# P1R4.net
KiCad netlist of a schematic drawn in EAGLE
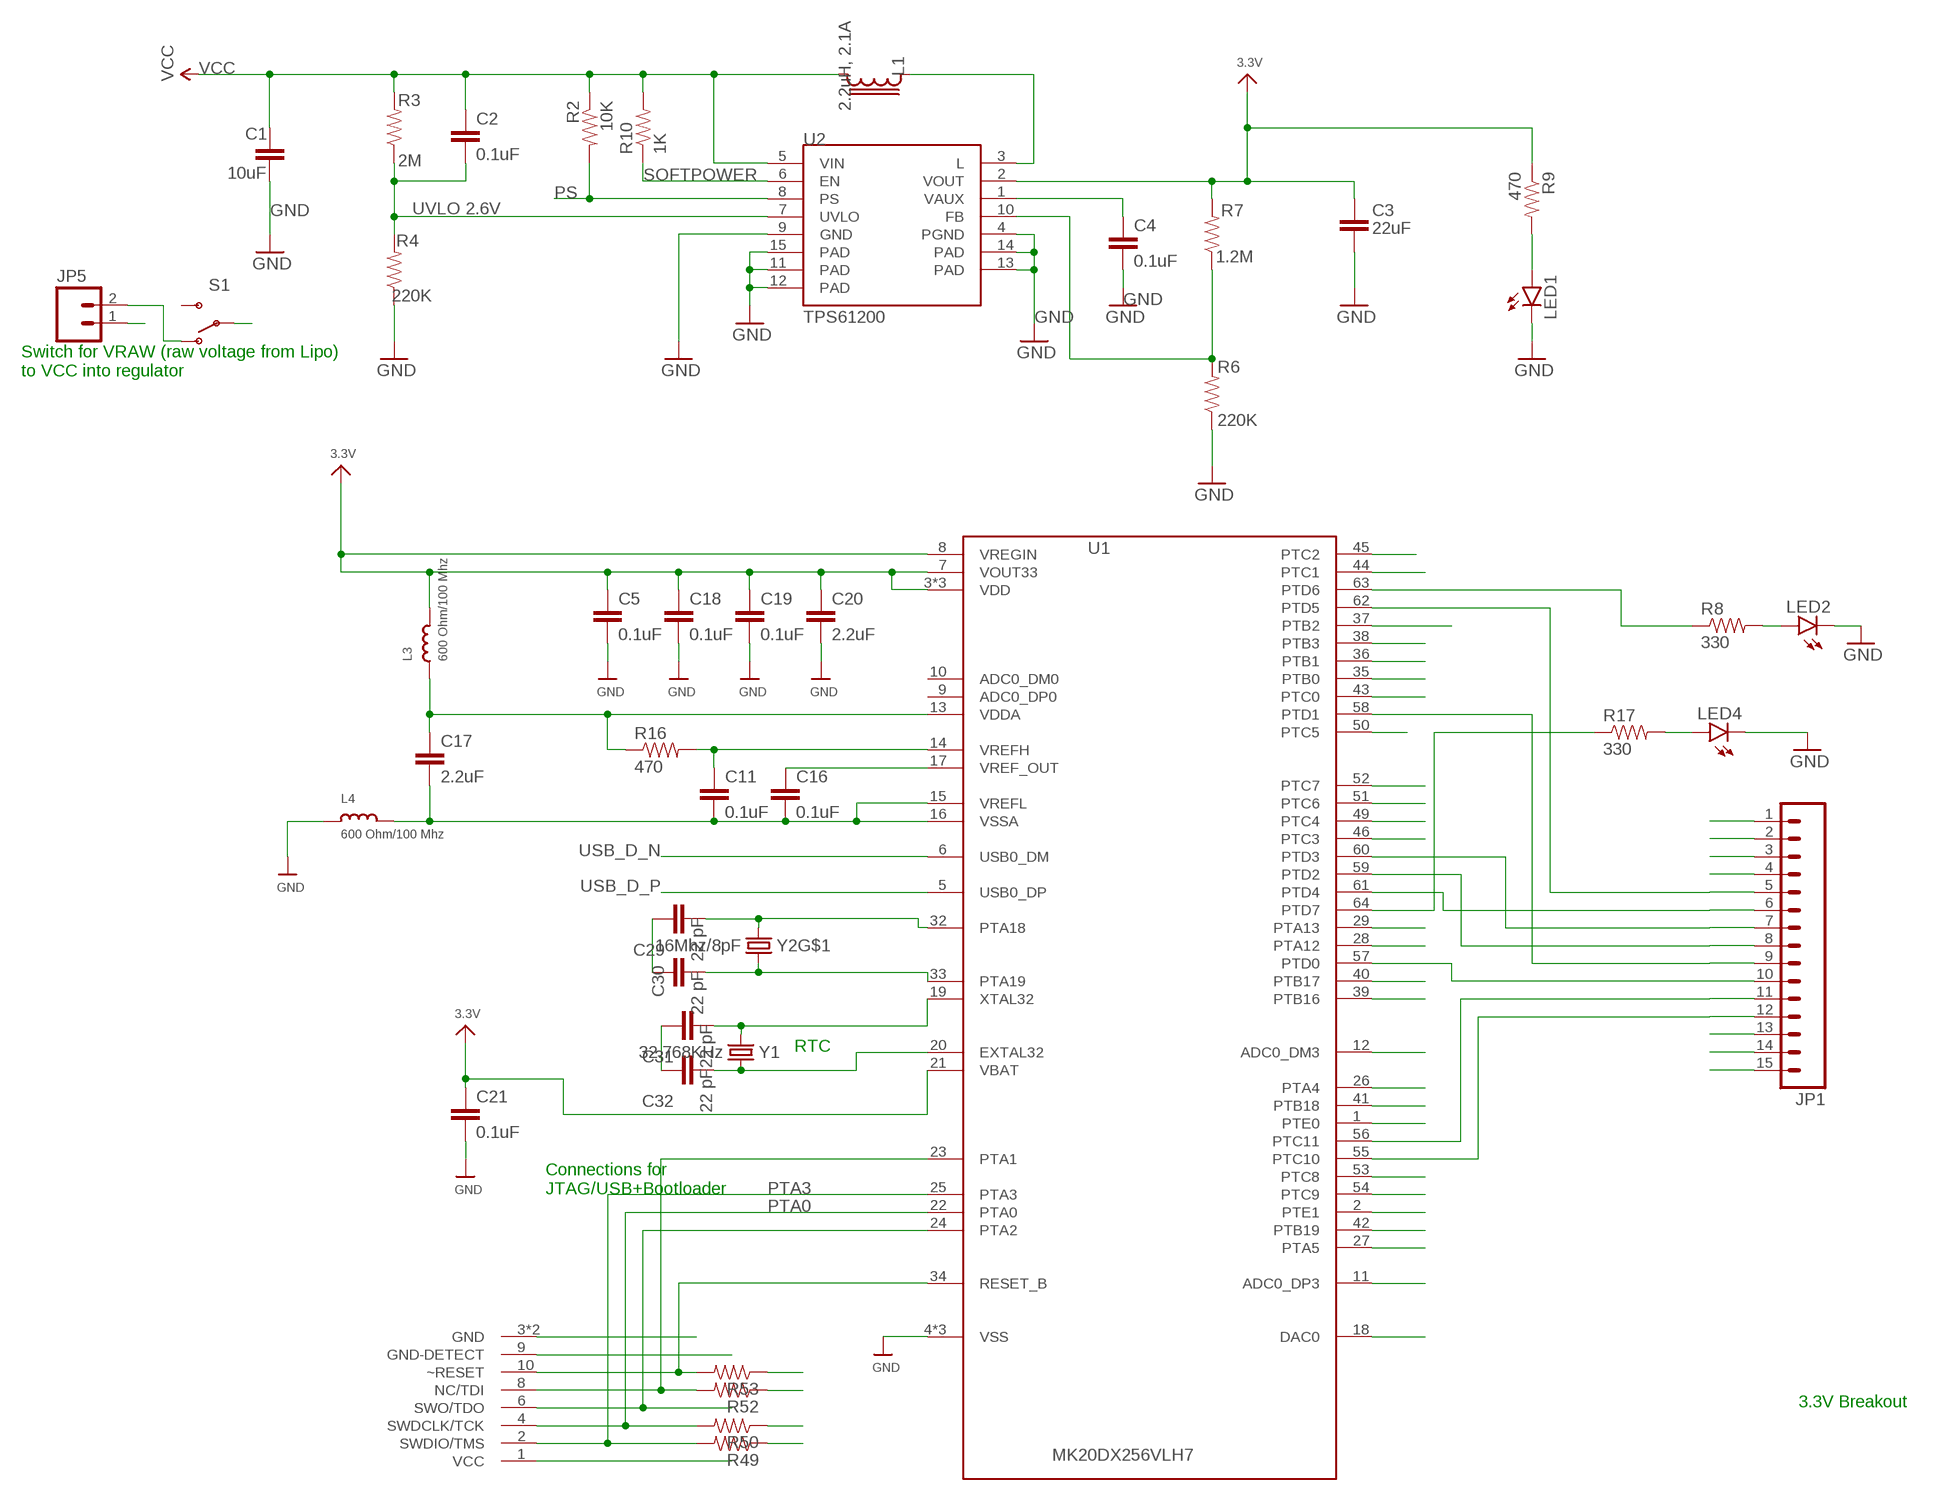
[diagram p0: schematic, sheet 1]
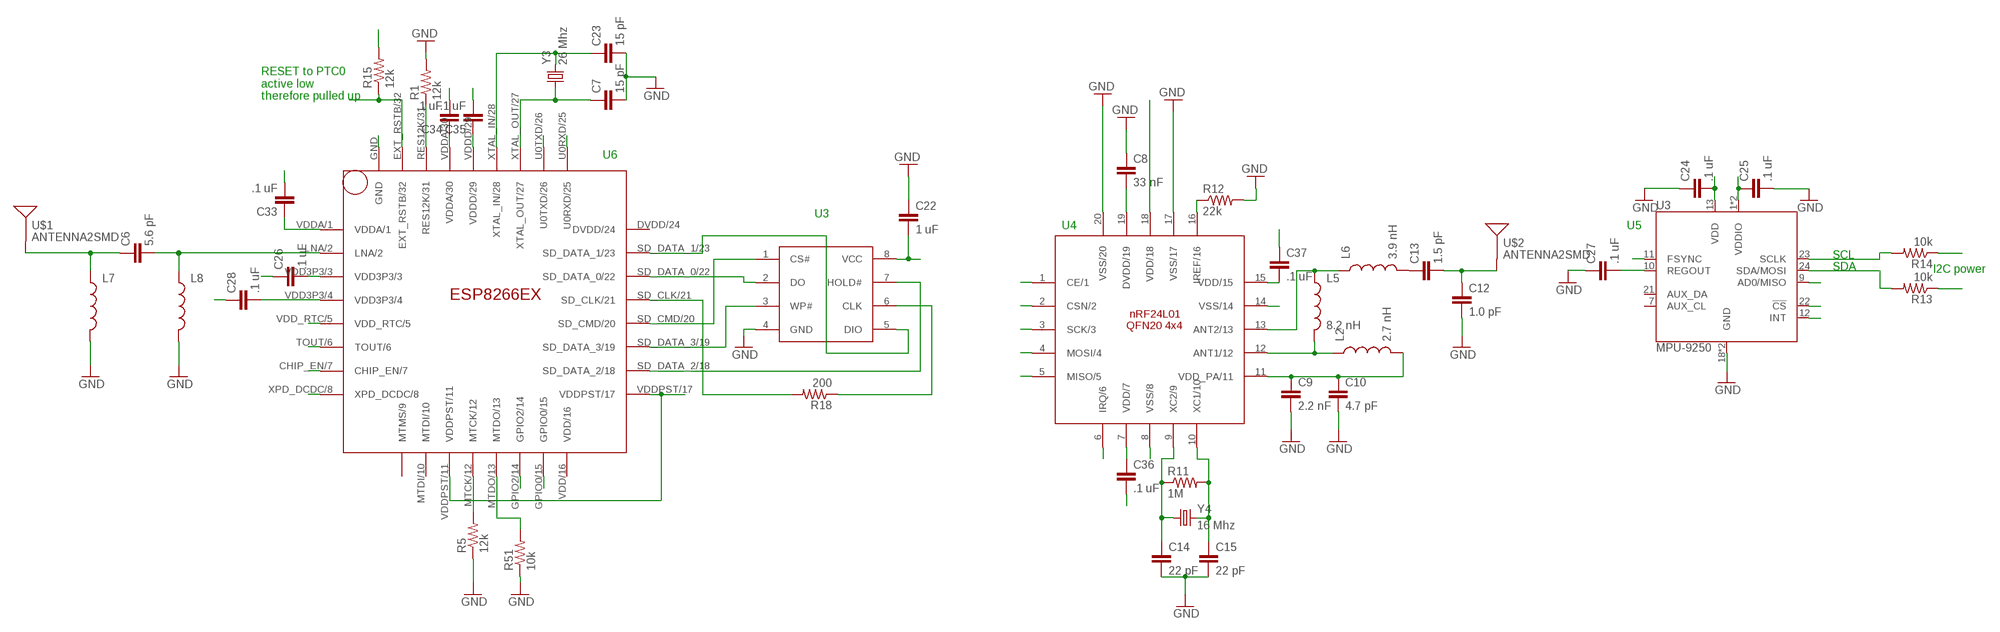
[diagram p1: schematic, sheet 2]
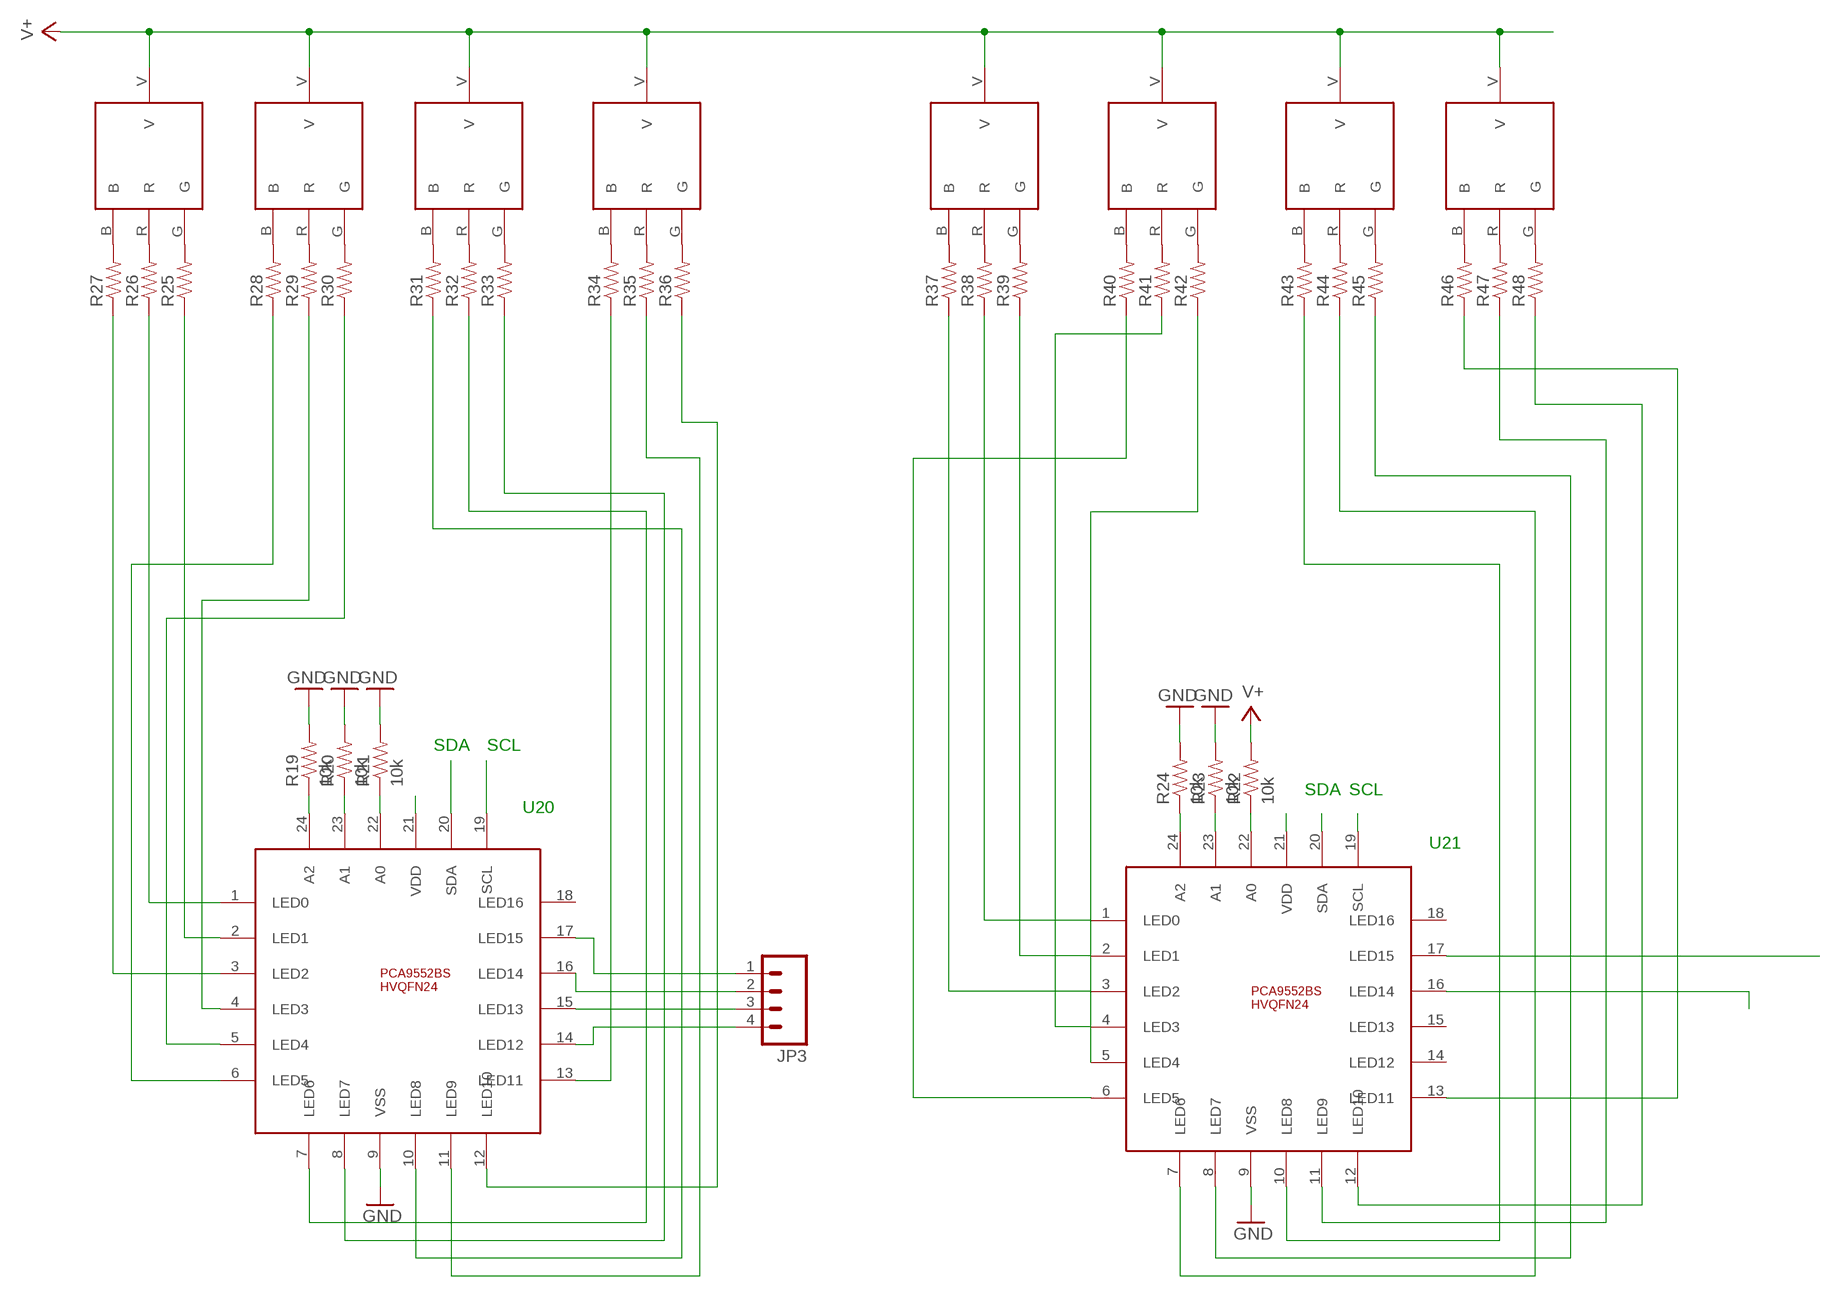
[diagram p2: schematic, sheet 3]

(export (version "E")
  (design (tool "Eeschema 10.0.6"))
  (components
    (comp (ref "C1")
      (value "10uF")
      (footprint "eagle-import:0603-CAP")
      (fields (field (name "MF") "Murata") (field (name "MPN") "GRM188R60J106ME47D"))
      (libsource (lib "eagle-import") (part "CAPACITOR-10UF"))
    )
    (comp (ref "C2")
      (value "0.1uF")
      (footprint "eagle-import:0603-CAP")
      (fields (field (name "MF") "Kemet") (field (name "MPN") "C0603C104J3RACTU"))
      (libsource (lib "eagle-import") (part "CAPACITOR-0.1UF"))
    )
    (comp (ref "C3")
      (value "22uF")
      (footprint "eagle-import:0603-CAP")
      (fields (field (name "MF") "Murata") (field (name "MPN") "GRM188R60J226MEA0D"))
      (libsource (lib "eagle-import") (part "CAPACITOR-22UF"))
    )
    (comp (ref "C4")
      (value "0.1uF")
      (footprint "eagle-import:0603-CAP")
      (fields (field (name "MF") "Kemet") (field (name "MPN") "C0603C104J3RACTU"))
      (libsource (lib "eagle-import") (part "CAPACITOR-0.1UF"))
    )
    (comp (ref "C5")
      (value "0.1uF")
      (footprint "eagle-import:0603-CAP")
      (fields (field (name "MF") "Kemet") (field (name "MPN") "C0603C104J3RACTU"))
      (libsource (lib "eagle-import") (part "CAPACITOR-0.1UF"))
    )
    (comp (ref "C11")
      (value "0.1uF")
      (footprint "eagle-import:0603-CAP")
      (fields (field (name "MF") "Kemet") (field (name "MPN") "C0603C104J3RACTU"))
      (libsource (lib "eagle-import") (part "CAPACITOR-0.1UF"))
    )
    (comp (ref "C16")
      (value "0.1uF")
      (footprint "eagle-import:0603-CAP")
      (fields (field (name "MF") "Kemet") (field (name "MPN") "C0603C104J3RACTU"))
      (libsource (lib "eagle-import") (part "CAPACITOR-0.1UF"))
    )
    (comp (ref "C17")
      (value "2.2uF")
      (footprint "eagle-import:0603-CAP")
      (fields (field (name "MF") "Kemet") (field (name "MPN") "C0603C225K4PACTU"))
      (libsource (lib "eagle-import") (part "CAPACITOR-2.2UF"))
    )
    (comp (ref "C18")
      (value "0.1uF")
      (footprint "eagle-import:0603-CAP")
      (fields (field (name "MF") "Kemet") (field (name "MPN") "C0603C104J3RACTU"))
      (libsource (lib "eagle-import") (part "CAPACITOR-0.1UF"))
    )
    (comp (ref "C19")
      (value "0.1uF")
      (footprint "eagle-import:0603-CAP")
      (fields (field (name "MF") "Kemet") (field (name "MPN") "C0603C104J3RACTU"))
      (libsource (lib "eagle-import") (part "CAPACITOR-0.1UF"))
    )
    (comp (ref "C20")
      (value "2.2uF")
      (footprint "eagle-import:0603-CAP")
      (fields (field (name "MF") "Kemet") (field (name "MPN") "C0603C225K4PACTU"))
      (libsource (lib "eagle-import") (part "CAPACITOR-2.2UF"))
    )
    (comp (ref "C21")
      (value "0.1uF")
      (footprint "eagle-import:0603-CAP")
      (fields (field (name "MF") "Kemet") (field (name "MPN") "C0603C104J3RACTU"))
      (libsource (lib "eagle-import") (part "CAPACITOR-0.1UF"))
    )
    (comp (ref "C29")
      (value "22 pF")
      (footprint "eagle-import:0603-CAP")
      (fields (field (name "MF") "Murata") (field (name "MPN") "GRM188R60J106ME47D"))
      (libsource (lib "eagle-import") (part "CAPACITOR-10UF"))
    )
    (comp (ref "C30")
      (value "22 pF")
      (footprint "eagle-import:0603-CAP")
      (fields (field (name "MF") "Murata") (field (name "MPN") "GRM188R60J106ME47D"))
      (libsource (lib "eagle-import") (part "CAPACITOR-10UF"))
    )
    (comp (ref "C31")
      (value "22 pF")
      (footprint "eagle-import:0603-CAP")
      (fields (field (name "MF") "Murata") (field (name "MPN") "GRM188R60J106ME47D"))
      (libsource (lib "eagle-import") (part "CAPACITOR-10UF"))
    )
    (comp (ref "C32")
      (value "22 pF")
      (footprint "eagle-import:0603-CAP")
      (fields (field (name "MF") "Murata") (field (name "MPN") "GRM188R60J106ME47D"))
      (libsource (lib "eagle-import") (part "CAPACITOR-10UF"))
    )
    (comp (ref "JP1")
      (value "M15")
      (footprint "eagle-import:1X15")
      (libsource (lib "eagle-import") (part "M15"))
    )
    (comp (ref "JP5")
      (value "M02PTH")
      (footprint "eagle-import:1X02")
      (libsource (lib "eagle-import") (part "M02PTH"))
    )
    (comp (ref "L1")
      (value "2.2uH, 2.1A")
      (footprint "eagle-import:LPS3015")
      (fields (field (name "MF") "Coilcraft") (field (name "MPN") "LPS3015-222MRB"))
      (libsource (lib "eagle-import") (part "LPS30152.2UH"))
    )
    (comp (ref "L3")
      (value "600 Ohm/100 Mhz")
      (footprint "eagle-import:0805")
      (fields (field (name "MF") "Taiyo Yuden") (field (name "MPN") "BK2125HM601-T"))
      (libsource (lib "eagle-import") (part "INDUCTOR-BK2125HM601-T"))
    )
    (comp (ref "L4")
      (value "600 Ohm/100 Mhz")
      (footprint "eagle-import:0805")
      (fields (field (name "MF") "Taiyo Yuden") (field (name "MPN") "BK2125HM601-T"))
      (libsource (lib "eagle-import") (part "INDUCTOR-BK2125HM601-T"))
    )
    (comp (ref "LED1")
      (value "LED-GREEN")
      (footprint "eagle-import:LED-0603")
      (fields (field (name "MF") "Avago") (field (name "MPN") "HSMG-C190"))
      (libsource (lib "eagle-import") (part "LED-GREEN"))
    )
    (comp (ref "LED2")
      (value "LED-GREEN")
      (footprint "eagle-import:LED-0603")
      (fields (field (name "MF") "Avago") (field (name "MPN") "HSMG-C190"))
      (libsource (lib "eagle-import") (part "LED-GREEN"))
    )
    (comp (ref "LED4")
      (value "LED-GREEN")
      (footprint "eagle-import:LED-0603")
      (fields (field (name "MF") "Avago") (field (name "MPN") "HSMG-C190"))
      (libsource (lib "eagle-import") (part "LED-GREEN"))
    )
    (comp (ref "R2")
      (value "10K")
      (footprint "eagle-import:0603-RES")
      (fields (field (name "MF") "Panasonic") (field (name "MPN") "ERJ-3GEYJ103V"))
      (libsource (lib "eagle-import") (part "RESISTOR-10K"))
    )
    (comp (ref "R3")
      (value "2M")
      (footprint "eagle-import:0603-RES")
      (fields (field (name "MF") "Panasonic") (field (name "MPN") "ERJ-3GEYJ205V"))
      (libsource (lib "eagle-import") (part "RESISTOR-2M"))
    )
    (comp (ref "R4")
      (value "220K")
      (footprint "eagle-import:0603-RES")
      (fields (field (name "MF") "Panasonic") (field (name "MPN") "ERJ-3GEYJ224V"))
      (libsource (lib "eagle-import") (part "RESISTOR-220K"))
    )
    (comp (ref "R6")
      (value "220K")
      (footprint "eagle-import:0603-RES")
      (fields (field (name "MF") "Panasonic") (field (name "MPN") "ERJ-3GEYJ224V"))
      (libsource (lib "eagle-import") (part "RESISTOR-220K"))
    )
    (comp (ref "R7")
      (value "1.2M")
      (footprint "eagle-import:0603-RES")
      (fields (field (name "MF") "Panasonic") (field (name "MPN") "ERJ-3GEYJ125V"))
      (libsource (lib "eagle-import") (part "RESISTOR-1.2M"))
    )
    (comp (ref "R8")
      (value "330")
      (footprint "eagle-import:0603-RES")
      (fields (field (name "MF") "Panasonic") (field (name "MPN") "ERJ-3GEYJ471V"))
      (libsource (lib "eagle-import") (part "RESISTOR-470"))
    )
    (comp (ref "R9")
      (value "470")
      (footprint "eagle-import:0603-RES")
      (fields (field (name "MF") "Panasonic") (field (name "MPN") "ERJ-3GEYJ471V"))
      (libsource (lib "eagle-import") (part "RESISTOR-470"))
    )
    (comp (ref "R10")
      (value "1K")
      (footprint "eagle-import:0603-RES")
      (fields (field (name "MF") "Panasonic") (field (name "MPN") "ERJ-3GEYJ102V"))
      (libsource (lib "eagle-import") (part "RESISTOR-1K"))
    )
    (comp (ref "R16")
      (value "470")
      (footprint "eagle-import:0603-RES")
      (fields (field (name "MF") "Panasonic") (field (name "MPN") "ERJ-3GEYJ471V"))
      (libsource (lib "eagle-import") (part "RESISTOR-470"))
    )
    (comp (ref "R17")
      (value "330")
      (footprint "eagle-import:0603-RES")
      (fields (field (name "MF") "Panasonic") (field (name "MPN") "ERJ-3GEYJ471V"))
      (libsource (lib "eagle-import") (part "RESISTOR-470"))
    )
    (comp (ref "R49")
      (value "RESISTOR0402-RES")
      (footprint "eagle-import:0402-RES")
      (libsource (lib "eagle-import") (part "RESISTOR0402-RES"))
    )
    (comp (ref "R50")
      (value "RESISTOR0402-RES")
      (footprint "eagle-import:0402-RES")
      (libsource (lib "eagle-import") (part "RESISTOR0402-RES"))
    )
    (comp (ref "R52")
      (value "RESISTOR0402-RES")
      (footprint "eagle-import:0402-RES")
      (libsource (lib "eagle-import") (part "RESISTOR0402-RES"))
    )
    (comp (ref "R53")
      (value "RESISTOR0402-RES")
      (footprint "eagle-import:0402-RES")
      (libsource (lib "eagle-import") (part "RESISTOR0402-RES"))
    )
    (comp (ref "S1")
      (value "SWITCH-SPDT-SMD-A")
      (footprint "eagle-import:SWITCH-SPST-SMD-A")
      (libsource (lib "eagle-import") (part "SWITCH-SPDT-SMD-A"))
    )
    (comp (ref "U$7")
      (value "2X5_0.05\"_CORTEX_DEBUGTH_NOKEY_UNSHROUDED")
      (footprint "eagle-import:2X5_0.05__TH_NS")
      (libsource (lib "eagle-import") (part "2X5_0.05{dblquote}_CORTEX_DEBUGTH_NOKEY_UNSHROUDED"))
    )
    (comp (ref "U1")
      (value "MK20DX256VLH7")
      (footprint "eagle-import:MK20DX256VLH7")
      (fields (field (name "MF") "Freescale"))
      (libsource (lib "eagle-import") (part "MK20DX256VLH7"))
    )
    (comp (ref "U2")
      (value "TPS61200")
      (footprint "eagle-import:QFN-10_PAD")
      (fields (field (name "MF") "Texas Instruments") (field (name "MPN") "TPS61200DRCR"))
      (libsource (lib "eagle-import") (part "TPS61200"))
    )
    (comp (ref "Y1")
      (value "32.768KHz")
      (footprint "eagle-import:CRYSTAL-TXC-7A")
      (fields (field (name "MF") "Epson Timing") (field (name "MPN") "FC-255 32.7680K-A3"))
      (libsource (lib "eagle-import") (part "CRYSTAL/32.768KHZ/SMD-TXC_7A"))
    )
    (comp (ref "Y2")
      (value "16Mhz/8pF")
      (footprint "eagle-import:CRYSTAL-SMD-5X3")
      (fields (field (name "MF") "ECS") (field (name "MPN") "ECS-160-8-30B-CKM"))
      (libsource (lib "eagle-import") (part "CRYSTAL/SMD-5X3-GND16MHZ/8PF"))
    )
    (comp (ref "JP3")
      (value "M04PTH")
      (footprint "eagle-import:1X04")
      (libsource (lib "eagle-import") (part "M04PTH"))
    )
    (comp (ref "R19")
      (value "10k")
      (footprint "eagle-import:0603-RES")
      (libsource (lib "eagle-import") (part "RESISTOR0603-RES"))
    )
    (comp (ref "R20")
      (value "10k")
      (footprint "eagle-import:0603-RES")
      (libsource (lib "eagle-import") (part "RESISTOR0603-RES"))
    )
    (comp (ref "R21")
      (value "10k")
      (footprint "eagle-import:0603-RES")
      (libsource (lib "eagle-import") (part "RESISTOR0603-RES"))
    )
    (comp (ref "R22")
      (value "10k")
      (footprint "eagle-import:0603-RES")
      (libsource (lib "eagle-import") (part "RESISTOR0603-RES"))
    )
    (comp (ref "R23")
      (value "10k")
      (footprint "eagle-import:0603-RES")
      (libsource (lib "eagle-import") (part "RESISTOR0603-RES"))
    )
    (comp (ref "R24")
      (value "10k")
      (footprint "eagle-import:0603-RES")
      (libsource (lib "eagle-import") (part "RESISTOR0603-RES"))
    )
    (comp (ref "R25")
      (value "RESISTOR0402-RES")
      (footprint "eagle-import:0402-RES")
      (libsource (lib "eagle-import") (part "RESISTOR0402-RES"))
    )
    (comp (ref "R26")
      (value "RESISTOR0402-RES")
      (footprint "eagle-import:0402-RES")
      (libsource (lib "eagle-import") (part "RESISTOR0402-RES"))
    )
    (comp (ref "R27")
      (value "RESISTOR0402-RES")
      (footprint "eagle-import:0402-RES")
      (libsource (lib "eagle-import") (part "RESISTOR0402-RES"))
    )
    (comp (ref "R28")
      (value "RESISTOR0402-RES")
      (footprint "eagle-import:0402-RES")
      (libsource (lib "eagle-import") (part "RESISTOR0402-RES"))
    )
    (comp (ref "R29")
      (value "RESISTOR0402-RES")
      (footprint "eagle-import:0402-RES")
      (libsource (lib "eagle-import") (part "RESISTOR0402-RES"))
    )
    (comp (ref "R30")
      (value "RESISTOR0402-RES")
      (footprint "eagle-import:0402-RES")
      (libsource (lib "eagle-import") (part "RESISTOR0402-RES"))
    )
    (comp (ref "R31")
      (value "RESISTOR0402-RES")
      (footprint "eagle-import:0402-RES")
      (libsource (lib "eagle-import") (part "RESISTOR0402-RES"))
    )
    (comp (ref "R32")
      (value "RESISTOR0402-RES")
      (footprint "eagle-import:0402-RES")
      (libsource (lib "eagle-import") (part "RESISTOR0402-RES"))
    )
    (comp (ref "R33")
      (value "RESISTOR0402-RES")
      (footprint "eagle-import:0402-RES")
      (libsource (lib "eagle-import") (part "RESISTOR0402-RES"))
    )
    (comp (ref "R34")
      (value "RESISTOR0402-RES")
      (footprint "eagle-import:0402-RES")
      (libsource (lib "eagle-import") (part "RESISTOR0402-RES"))
    )
    (comp (ref "R35")
      (value "RESISTOR0402-RES")
      (footprint "eagle-import:0402-RES")
      (libsource (lib "eagle-import") (part "RESISTOR0402-RES"))
    )
    (comp (ref "R36")
      (value "RESISTOR0402-RES")
      (footprint "eagle-import:0402-RES")
      (libsource (lib "eagle-import") (part "RESISTOR0402-RES"))
    )
    (comp (ref "R37")
      (value "RESISTOR0402-RES")
      (footprint "eagle-import:0402-RES")
      (libsource (lib "eagle-import") (part "RESISTOR0402-RES"))
    )
    (comp (ref "R38")
      (value "RESISTOR0402-RES")
      (footprint "eagle-import:0402-RES")
      (libsource (lib "eagle-import") (part "RESISTOR0402-RES"))
    )
    (comp (ref "R39")
      (value "RESISTOR0402-RES")
      (footprint "eagle-import:0402-RES")
      (libsource (lib "eagle-import") (part "RESISTOR0402-RES"))
    )
    (comp (ref "R40")
      (value "RESISTOR0402-RES")
      (footprint "eagle-import:0402-RES")
      (libsource (lib "eagle-import") (part "RESISTOR0402-RES"))
    )
    (comp (ref "R41")
      (value "RESISTOR0402-RES")
      (footprint "eagle-import:0402-RES")
      (libsource (lib "eagle-import") (part "RESISTOR0402-RES"))
    )
    (comp (ref "R42")
      (value "RESISTOR0402-RES")
      (footprint "eagle-import:0402-RES")
      (libsource (lib "eagle-import") (part "RESISTOR0402-RES"))
    )
    (comp (ref "R43")
      (value "RESISTOR0402-RES")
      (footprint "eagle-import:0402-RES")
      (libsource (lib "eagle-import") (part "RESISTOR0402-RES"))
    )
    (comp (ref "R44")
      (value "RESISTOR0402-RES")
      (footprint "eagle-import:0402-RES")
      (libsource (lib "eagle-import") (part "RESISTOR0402-RES"))
    )
    (comp (ref "R45")
      (value "RESISTOR0402-RES")
      (footprint "eagle-import:0402-RES")
      (libsource (lib "eagle-import") (part "RESISTOR0402-RES"))
    )
    (comp (ref "R46")
      (value "RESISTOR0402-RES")
      (footprint "eagle-import:0402-RES")
      (libsource (lib "eagle-import") (part "RESISTOR0402-RES"))
    )
    (comp (ref "R47")
      (value "RESISTOR0402-RES")
      (footprint "eagle-import:0402-RES")
      (libsource (lib "eagle-import") (part "RESISTOR0402-RES"))
    )
    (comp (ref "R48")
      (value "RESISTOR0402-RES")
      (footprint "eagle-import:0402-RES")
      (libsource (lib "eagle-import") (part "RESISTOR0402-RES"))
    )
    (comp (ref "U$8")
      (value "LTST-C19FD1WT")
      (footprint "eagle-import:LTST-C19FD1WT")
      (libsource (lib "eagle-import") (part "LTST-C19FD1WT"))
    )
    (comp (ref "U$11")
      (value "LTST-C19FD1WT")
      (footprint "eagle-import:LTST-C19FD1WT")
      (libsource (lib "eagle-import") (part "LTST-C19FD1WT"))
    )
    (comp (ref "U$13")
      (value "LTST-C19FD1WT")
      (footprint "eagle-import:LTST-C19FD1WT")
      (libsource (lib "eagle-import") (part "LTST-C19FD1WT"))
    )
    (comp (ref "U$14")
      (value "LTST-C19FD1WT")
      (footprint "eagle-import:LTST-C19FD1WT")
      (libsource (lib "eagle-import") (part "LTST-C19FD1WT"))
    )
    (comp (ref "U$15")
      (value "LTST-C19FD1WT")
      (footprint "eagle-import:LTST-C19FD1WT")
      (libsource (lib "eagle-import") (part "LTST-C19FD1WT"))
    )
    (comp (ref "U$16")
      (value "LTST-C19FD1WT")
      (footprint "eagle-import:LTST-C19FD1WT")
      (libsource (lib "eagle-import") (part "LTST-C19FD1WT"))
    )
    (comp (ref "U$17")
      (value "LTST-C19FD1WT")
      (footprint "eagle-import:LTST-C19FD1WT")
      (libsource (lib "eagle-import") (part "LTST-C19FD1WT"))
    )
    (comp (ref "U$18")
      (value "LTST-C19FD1WT")
      (footprint "eagle-import:LTST-C19FD1WT")
      (libsource (lib "eagle-import") (part "LTST-C19FD1WT"))
    )
    (comp (ref "U$20")
      (value "PCA9552BS")
      (footprint "eagle-import:HVQFN24")
      (libsource (lib "eagle-import") (part "PCA9552BS"))
    )
    (comp (ref "U$21")
      (value "PCA9552BS")
      (footprint "eagle-import:HVQFN24")
      (libsource (lib "eagle-import") (part "PCA9552BS"))
    )
    (comp (ref "C6")
      (value "5.6 pF")
      (footprint "eagle-import:0603-CAP")
      (libsource (lib "eagle-import") (part "CAP0603-CAP"))
    )
    (comp (ref "C7")
      (value "15 pF")
      (footprint "eagle-import:0603-CAP")
      (libsource (lib "eagle-import") (part "CAP0603-CAP"))
    )
    (comp (ref "C8")
      (value "33 nF")
      (footprint "eagle-import:0603-CAP")
      (libsource (lib "eagle-import") (part "CAP0603-CAP"))
    )
    (comp (ref "C9")
      (value "2.2 nF")
      (footprint "eagle-import:0603-CAP")
      (libsource (lib "eagle-import") (part "CAP0603-CAP"))
    )
    (comp (ref "C10")
      (value "4.7 pF")
      (footprint "eagle-import:0603-CAP")
      (libsource (lib "eagle-import") (part "CAP0603-CAP"))
    )
    (comp (ref "C12")
      (value "1.0 pF")
      (footprint "eagle-import:0603-CAP")
      (libsource (lib "eagle-import") (part "CAP0603-CAP"))
    )
    (comp (ref "C13")
      (value "1.5 pF")
      (footprint "eagle-import:0603-CAP")
      (libsource (lib "eagle-import") (part "CAP0603-CAP"))
    )
    (comp (ref "C14")
      (value "22 pF")
      (footprint "eagle-import:0603-CAP")
      (libsource (lib "eagle-import") (part "CAP0603-CAP"))
    )
    (comp (ref "C15")
      (value "22 pF")
      (footprint "eagle-import:0603-CAP")
      (libsource (lib "eagle-import") (part "CAP0603-CAP"))
    )
    (comp (ref "C22")
      (value "1 uF")
      (footprint "eagle-import:0603-CAP")
      (libsource (lib "eagle-import") (part "CAP0603-CAP"))
    )
    (comp (ref "C23")
      (value "15 pF")
      (footprint "eagle-import:0603-CAP")
      (libsource (lib "eagle-import") (part "CAP0603-CAP"))
    )
    (comp (ref "C24")
      (value ".1 uF")
      (footprint "eagle-import:0603-CAP")
      (libsource (lib "eagle-import") (part "CAP0603-CAP"))
    )
    (comp (ref "C25")
      (value ".1 uF")
      (footprint "eagle-import:0603-CAP")
      (libsource (lib "eagle-import") (part "CAP0603-CAP"))
    )
    (comp (ref "C26")
      (value ".1 uF")
      (footprint "eagle-import:0603-CAP")
      (libsource (lib "eagle-import") (part "CAP0603-CAP"))
    )
    (comp (ref "C27")
      (value ".1 uF")
      (footprint "eagle-import:0603-CAP")
      (libsource (lib "eagle-import") (part "CAP0603-CAP"))
    )
    (comp (ref "C28")
      (value ".1 uF")
      (footprint "eagle-import:0603-CAP")
      (libsource (lib "eagle-import") (part "CAP0603-CAP"))
    )
    (comp (ref "C33")
      (value ".1 uF")
      (footprint "eagle-import:0603-CAP")
      (libsource (lib "eagle-import") (part "CAP0603-CAP"))
    )
    (comp (ref "C34")
      (value ".1 uF")
      (footprint "eagle-import:0603-CAP")
      (libsource (lib "eagle-import") (part "CAP0603-CAP"))
    )
    (comp (ref "C35")
      (value ".1 uF")
      (footprint "eagle-import:0603-CAP")
      (libsource (lib "eagle-import") (part "CAP0603-CAP"))
    )
    (comp (ref "C36")
      (value ".1 uF")
      (footprint "eagle-import:0603-CAP")
      (libsource (lib "eagle-import") (part "CAP0603-CAP"))
    )
    (comp (ref "C37")
      (value ".1 uF")
      (footprint "eagle-import:0603-CAP")
      (libsource (lib "eagle-import") (part "CAP0603-CAP"))
    )
    (comp (ref "L2")
      (value "2.7 nH")
      (footprint "eagle-import:C0402")
      (libsource (lib "eagle-import") (part "INDUCTOR0402"))
    )
    (comp (ref "L5")
      (value "8.2 nH")
      (footprint "eagle-import:C0402")
      (libsource (lib "eagle-import") (part "INDUCTOR0402"))
    )
    (comp (ref "L6")
      (value "3.9 nH")
      (footprint "eagle-import:C0402")
      (libsource (lib "eagle-import") (part "INDUCTOR0402"))
    )
    (comp (ref "L7")
      (value "INDUCTOR30OHM,1.8A")
      (footprint "eagle-import:0603")
      (libsource (lib "eagle-import") (part "INDUCTOR30OHM,1.8A"))
    )
    (comp (ref "L8")
      (value "INDUCTOR30OHM,1.8A")
      (footprint "eagle-import:0603")
      (libsource (lib "eagle-import") (part "INDUCTOR30OHM,1.8A"))
    )
    (comp (ref "R1")
      (value "12k")
      (footprint "eagle-import:0603-RES")
      (libsource (lib "eagle-import") (part "SparkFun-Resistors_RESISTOR0603-RES"))
    )
    (comp (ref "R5")
      (value "12k")
      (footprint "eagle-import:0603-RES")
      (libsource (lib "eagle-import") (part "SparkFun-Resistors_RESISTOR0603-RES"))
    )
    (comp (ref "R11")
      (value "1M")
      (footprint "eagle-import:0603-RES")
      (libsource (lib "eagle-import") (part "SparkFun-Resistors_RESISTOR0603-RES"))
    )
    (comp (ref "R12")
      (value "22k")
      (footprint "eagle-import:0603-RES")
      (libsource (lib "eagle-import") (part "SparkFun-Resistors_RESISTOR0603-RES"))
    )
    (comp (ref "R13")
      (value "10k")
      (footprint "eagle-import:0603-RES")
      (libsource (lib "eagle-import") (part "SparkFun-Resistors_RESISTOR0603-RES"))
    )
    (comp (ref "R14")
      (value "10k")
      (footprint "eagle-import:0603-RES")
      (libsource (lib "eagle-import") (part "SparkFun-Resistors_RESISTOR0603-RES"))
    )
    (comp (ref "R15")
      (value "12k")
      (footprint "eagle-import:0603-RES")
      (libsource (lib "eagle-import") (part "SparkFun-Resistors_RESISTOR0603-RES"))
    )
    (comp (ref "R18")
      (value "200")
      (footprint "eagle-import:0603-RES")
      (libsource (lib "eagle-import") (part "SparkFun-Resistors_RESISTOR0603-RES"))
    )
    (comp (ref "R51")
      (value "10k")
      (footprint "eagle-import:0603-RES")
      (libsource (lib "eagle-import") (part "SparkFun-Resistors_RESISTOR0603-RES"))
    )
    (comp (ref "U$1")
      (value "ANTENNA2SMD")
      (footprint "eagle-import:ANTENNA-CHIP2")
      (libsource (lib "eagle-import") (part "ANTENNA2SMD"))
    )
    (comp (ref "U$2")
      (value "ANTENNA2SMD")
      (footprint "eagle-import:ANTENNA-CHIP2")
      (libsource (lib "eagle-import") (part "ANTENNA2SMD"))
    )
    (comp (ref "U$3")
      (value "25Q40")
      (footprint "eagle-import:SOP8")
      (libsource (lib "eagle-import") (part "25Q40"))
    )
    (comp (ref "U$4")
      (value "NRF24L01")
      (footprint "eagle-import:QFN20(4X4)")
      (libsource (lib "eagle-import") (part "NRF24L01"))
    )
    (comp (ref "U$6")
      (value "ESP8266EX")
      (footprint "eagle-import:QFN32")
      (libsource (lib "eagle-import") (part "ESP8266EX"))
    )
    (comp (ref "U3")
      (value "MPU-9250")
      (footprint "eagle-import:QFN-24_3MM")
      (libsource (lib "eagle-import") (part "MPU-9250"))
    )
    (comp (ref "Y3")
      (value "26 Mhz")
      (footprint "eagle-import:CRYSTAL-SMD-5X3")
      (libsource (lib "eagle-import") (part "CRYSTAL5X3"))
    )
    (comp (ref "Y4")
      (value "16 Mhz")
      (footprint "eagle-import:CRYSTAL-SMD-5X3")
      (libsource (lib "eagle-import") (part "CRYSTAL5X3"))
    )
  )
  (nets
    (net (code "1") (name "3.3V") (class "Default")
      (node (ref "C18") (pin "1") (pinfunction "1_1") (pintype "passive"))
      (node (ref "C19") (pin "1") (pinfunction "1_1") (pintype "passive"))
      (node (ref "C20") (pin "1") (pinfunction "1_1") (pintype "passive"))
      (node (ref "C21") (pin "1") (pinfunction "1_1") (pintype "passive"))
      (node (ref "C22") (pin "2") (pinfunction "2_2") (pintype "passive"))
      (node (ref "C24") (pin "2") (pinfunction "2_2") (pintype "passive"))
      (node (ref "C25") (pin "1") (pinfunction "1_1") (pintype "passive"))
      (node (ref "C26") (pin "2") (pinfunction "2_2") (pintype "passive"))
      (node (ref "C28") (pin "2") (pinfunction "2_2") (pintype "passive"))
      (node (ref "C3") (pin "1") (pinfunction "1_1") (pintype "passive"))
      (node (ref "C33") (pin "1") (pinfunction "1_1") (pintype "passive"))
      (node (ref "C34") (pin "1") (pinfunction "1_1") (pintype "passive"))
      (node (ref "C35") (pin "1") (pinfunction "1_1") (pintype "passive"))
      (node (ref "C36") (pin "1") (pinfunction "1_1") (pintype "passive"))
      (node (ref "C37") (pin "2") (pinfunction "2_2") (pintype "passive"))
      (node (ref "C5") (pin "1") (pinfunction "1_1") (pintype "passive"))
      (node (ref "JP1") (pin "13") (pinfunction "13_13") (pintype "passive"))
      (node (ref "JP1") (pin "14") (pinfunction "14_14") (pintype "passive"))
      (node (ref "JP1") (pin "15") (pinfunction "15_15") (pintype "passive"))
      (node (ref "L3") (pin "2") (pinfunction "2_2") (pintype "passive"))
      (node (ref "R13") (pin "1") (pinfunction "1_1") (pintype "passive"))
      (node (ref "R14") (pin "1") (pinfunction "1_1") (pintype "passive"))
      (node (ref "R15") (pin "2") (pinfunction "2_2") (pintype "passive"))
      (node (ref "R22") (pin "2") (pinfunction "2_2") (pintype "passive"))
      (node (ref "R49") (pin "1") (pinfunction "1_1") (pintype "passive"))
      (node (ref "R52") (pin "1") (pinfunction "1_1") (pintype "passive"))
      (node (ref "R53") (pin "1") (pinfunction "1_1") (pintype "passive"))
      (node (ref "R7") (pin "2") (pinfunction "2_2") (pintype "passive"))
      (node (ref "R9") (pin "1") (pinfunction "1_1") (pintype "passive"))
      (node (ref "U$11") (pin "V") (pinfunction "V_V") (pintype "bidirectional"))
      (node (ref "U$13") (pin "V") (pinfunction "V_V") (pintype "bidirectional"))
      (node (ref "U$14") (pin "V") (pinfunction "V_V") (pintype "bidirectional"))
      (node (ref "U$15") (pin "V") (pinfunction "V_V") (pintype "bidirectional"))
      (node (ref "U$16") (pin "V") (pinfunction "V_V") (pintype "bidirectional"))
      (node (ref "U$17") (pin "V") (pinfunction "V_V") (pintype "bidirectional"))
      (node (ref "U$18") (pin "V") (pinfunction "V_V") (pintype "bidirectional"))
      (node (ref "U$20") (pin "21") (pinfunction "VDD_21") (pintype "bidirectional"))
      (node (ref "U$21") (pin "21") (pinfunction "VDD_21") (pintype "bidirectional"))
      (node (ref "U$3") (pin "8") (pinfunction "VCC_8") (pintype "bidirectional"))
      (node (ref "U$4") (pin "15") (pinfunction "VDD/15_15") (pintype "bidirectional"))
      (node (ref "U$4") (pin "18") (pinfunction "VDD/18_18") (pintype "bidirectional"))
      (node (ref "U$4") (pin "7") (pinfunction "VDD/7_7") (pintype "bidirectional"))
      (node (ref "U$6") (pin "VDD3P3/3") (pinfunction "VDD3P3/3_VDD3P3/3") (pintype "bidirectional"))
      (node (ref "U$6") (pin "VDD3P3/4") (pinfunction "VDD3P3/4_VDD3P3/4") (pintype "bidirectional"))
      (node (ref "U$6") (pin "VDDA/1") (pinfunction "VDDA/1_VDDA/1") (pintype "bidirectional"))
      (node (ref "U$6") (pin "VDDA/30") (pinfunction "VDDA/30_VDDA/30") (pintype "bidirectional"))
      (node (ref "U$6") (pin "VDDD/29") (pinfunction "VDDD/29_VDDD/29") (pintype "bidirectional"))
      (node (ref "U$6") (pin "VDDPST/11") (pinfunction "VDDPST/11_VDDPST/11") (pintype "bidirectional"))
      (node (ref "U$6") (pin "VDDPST/17") (pinfunction "VDDPST/17_VDDPST/17") (pintype "bidirectional"))
      (node (ref "U$7") (pin "1") (pinfunction "VCC_1") (pintype "bidirectional"))
      (node (ref "U$8") (pin "V") (pinfunction "V_V") (pintype "bidirectional"))
      (node (ref "U1") (pin "21") (pinfunction "VBAT_21") (pintype "bidirectional"))
      (node (ref "U1") (pin "3") (pinfunction "VDD_3") (pintype "bidirectional"))
      (node (ref "U1") (pin "30") (pinfunction "VDD_30") (pintype "bidirectional"))
      (node (ref "U1") (pin "48") (pinfunction "VDD_48") (pintype "bidirectional"))
      (node (ref "U1") (pin "7") (pinfunction "VOUT33_7") (pintype "bidirectional"))
      (node (ref "U1") (pin "8") (pinfunction "VREGIN_8") (pintype "bidirectional"))
      (node (ref "U2") (pin "2") (pinfunction "VOUT_2") (pintype "passive"))
      (node (ref "U3") (pin "1") (pinfunction "VDDIO_1") (pintype "bidirectional"))
      (node (ref "U3") (pin "13") (pinfunction "VDD_13") (pintype "bidirectional"))
      (node (ref "U3") (pin "22") (pinfunction "~{CS}_22") (pintype "bidirectional"))
      (node (ref "U3") (pin "8") (pinfunction "VDDIO_8") (pintype "bidirectional"))
    )
    (net (code "2") (name "AD0") (class "Default")
      (node (ref "U1") (pin "45") (pinfunction "PTC2_45") (pintype "bidirectional"))
      (node (ref "U3") (pin "9") (pinfunction "AD0/MISO_9") (pintype "bidirectional"))
    )
    (net (code "3") (name "GND") (class "Default")
      (node (ref "C1") (pin "2") (pinfunction "2_2") (pintype "passive"))
      (node (ref "C10") (pin "2") (pinfunction "2_2") (pintype "passive"))
      (node (ref "C12") (pin "2") (pinfunction "2_2") (pintype "passive"))
      (node (ref "C14") (pin "2") (pinfunction "2_2") (pintype "passive"))
      (node (ref "C15") (pin "2") (pinfunction "2_2") (pintype "passive"))
      (node (ref "C18") (pin "2") (pinfunction "2_2") (pintype "passive"))
      (node (ref "C19") (pin "2") (pinfunction "2_2") (pintype "passive"))
      (node (ref "C20") (pin "2") (pinfunction "2_2") (pintype "passive"))
      (node (ref "C21") (pin "2") (pinfunction "2_2") (pintype "passive"))
      (node (ref "C22") (pin "1") (pinfunction "1_1") (pintype "passive"))
      (node (ref "C23") (pin "2") (pinfunction "2_2") (pintype "passive"))
      (node (ref "C24") (pin "1") (pinfunction "1_1") (pintype "passive"))
      (node (ref "C25") (pin "2") (pinfunction "2_2") (pintype "passive"))
      (node (ref "C26") (pin "1") (pinfunction "1_1") (pintype "passive"))
      (node (ref "C27") (pin "1") (pinfunction "1_1") (pintype "passive"))
      (node (ref "C28") (pin "1") (pinfunction "1_1") (pintype "passive"))
      (node (ref "C29") (pin "1") (pinfunction "1_1") (pintype "passive"))
      (node (ref "C3") (pin "2") (pinfunction "2_2") (pintype "passive"))
      (node (ref "C30") (pin "1") (pinfunction "1_1") (pintype "passive"))
      (node (ref "C31") (pin "1") (pinfunction "1_1") (pintype "passive"))
      (node (ref "C32") (pin "1") (pinfunction "1_1") (pintype "passive"))
      (node (ref "C33") (pin "2") (pinfunction "2_2") (pintype "passive"))
      (node (ref "C34") (pin "2") (pinfunction "2_2") (pintype "passive"))
      (node (ref "C35") (pin "2") (pinfunction "2_2") (pintype "passive"))
      (node (ref "C36") (pin "2") (pinfunction "2_2") (pintype "passive"))
      (node (ref "C37") (pin "1") (pinfunction "1_1") (pintype "passive"))
      (node (ref "C4") (pin "2") (pinfunction "2_2") (pintype "passive"))
      (node (ref "C5") (pin "2") (pinfunction "2_2") (pintype "passive"))
      (node (ref "C7") (pin "2") (pinfunction "2_2") (pintype "passive"))
      (node (ref "C8") (pin "1") (pinfunction "1_1") (pintype "passive"))
      (node (ref "C9") (pin "2") (pinfunction "2_2") (pintype "passive"))
      (node (ref "JP1") (pin "1") (pinfunction "1_1") (pintype "passive"))
      (node (ref "JP1") (pin "2") (pinfunction "2_2") (pintype "passive"))
      (node (ref "JP1") (pin "3") (pinfunction "3_3") (pintype "passive"))
      (node (ref "JP1") (pin "4") (pinfunction "4_4") (pintype "passive"))
      (node (ref "JP5") (pin "1") (pinfunction "1_1") (pintype "passive"))
      (node (ref "L4") (pin "1") (pinfunction "1_1") (pintype "passive"))
      (node (ref "L7") (pin "2") (pinfunction "2_2") (pintype "passive"))
      (node (ref "L8") (pin "2") (pinfunction "2_2") (pintype "passive"))
      (node (ref "LED1") (pin "C") (pinfunction "C_C") (pintype "passive"))
      (node (ref "LED2") (pin "C") (pinfunction "C_C") (pintype "passive"))
      (node (ref "LED4") (pin "C") (pinfunction "C_C") (pintype "passive"))
      (node (ref "R1") (pin "2") (pinfunction "2_2") (pintype "passive"))
      (node (ref "R12") (pin "2") (pinfunction "2_2") (pintype "passive"))
      (node (ref "R19") (pin "2") (pinfunction "2_2") (pintype "passive"))
      (node (ref "R20") (pin "2") (pinfunction "2_2") (pintype "passive"))
      (node (ref "R21") (pin "2") (pinfunction "2_2") (pintype "passive"))
      (node (ref "R23") (pin "2") (pinfunction "2_2") (pintype "passive"))
      (node (ref "R24") (pin "2") (pinfunction "2_2") (pintype "passive"))
      (node (ref "R4") (pin "1") (pinfunction "1_1") (pintype "passive"))
      (node (ref "R5") (pin "1") (pinfunction "1_1") (pintype "passive"))
      (node (ref "R50") (pin "1") (pinfunction "1_1") (pintype "passive"))
      (node (ref "R51") (pin "1") (pinfunction "1_1") (pintype "passive"))
      (node (ref "R6") (pin "1") (pinfunction "1_1") (pintype "passive"))
      (node (ref "U$20") (pin "9") (pinfunction "VSS_9") (pintype "bidirectional"))
      (node (ref "U$21") (pin "9") (pinfunction "VSS_9") (pintype "bidirectional"))
      (node (ref "U$3") (pin "4") (pinfunction "GND_4") (pintype "bidirectional"))
      (node (ref "U$4") (pin "14") (pinfunction "VSS/14_14") (pintype "bidirectional"))
      (node (ref "U$4") (pin "17") (pinfunction "VSS/17_17") (pintype "bidirectional"))
      (node (ref "U$4") (pin "20") (pinfunction "VSS/20_20") (pintype "bidirectional"))
      (node (ref "U$4") (pin "8") (pinfunction "VSS/8_8") (pintype "bidirectional"))
      (node (ref "U$6") (pin "GND") (pinfunction "GND_GND") (pintype "bidirectional"))
      (node (ref "U$7") (pin "3") (pinfunction "GND_3") (pintype "bidirectional"))
      (node (ref "U$7") (pin "5") (pinfunction "GND_5") (pintype "bidirectional"))
      (node (ref "U$7") (pin "9") (pinfunction "GND-DETECT_9") (pintype "bidirectional"))
      (node (ref "U1") (pin "31") (pinfunction "VSS_31") (pintype "bidirectional"))
      (node (ref "U1") (pin "4") (pinfunction "VSS_4") (pintype "bidirectional"))
      (node (ref "U1") (pin "47") (pinfunction "VSS_47") (pintype "bidirectional"))
      (node (ref "U2") (pin "11") (pinfunction "PAD_11") (pintype "power_in"))
      (node (ref "U2") (pin "12") (pinfunction "PAD_12") (pintype "power_in"))
      (node (ref "U2") (pin "13") (pinfunction "PAD_13") (pintype "power_in"))
      (node (ref "U2") (pin "14") (pinfunction "PAD_14") (pintype "power_in"))
      (node (ref "U2") (pin "15") (pinfunction "PAD_15") (pintype "power_in"))
      (node (ref "U2") (pin "4") (pinfunction "PGND_4") (pintype "power_in"))
      (node (ref "U2") (pin "9") (pinfunction "GND_9") (pintype "power_in"))
      (node (ref "U3") (pin "18") (pinfunction "GND_18") (pintype "bidirectional"))
      (node (ref "U3") (pin "20") (pinfunction "GND_20") (pintype "bidirectional"))
    )
    (net (code "4") (name "Net-(C6-Pad2)") (class "Default")
      (node (ref "C6") (pin "2") (pinfunction "2_2") (pintype "passive"))
      (node (ref "L8") (pin "1") (pinfunction "1_1") (pintype "passive"))
      (node (ref "U$6") (pin "LNA/2") (pinfunction "LNA/2_LNA/2") (pintype "bidirectional"))
    )
    (net (code "5") (name "Net-(C7-Pad1)") (class "Default")
      (node (ref "C7") (pin "1") (pinfunction "1_1") (pintype "passive"))
      (node (ref "U$6") (pin "XTAL_OUT/27") (pinfunction "XTAL_OUT/27_XTAL_OUT/27") (pintype "bidirectional"))
      (node (ref "Y3") (pin "1") (pinfunction "1_1") (pintype "passive"))
    )
    (net (code "6") (name "Net-(C13-Pad1)") (class "Default")
      (node (ref "C13") (pin "1") (pinfunction "1_1") (pintype "passive"))
      (node (ref "L6") (pin "2") (pinfunction "2_2") (pintype "passive"))
    )
    (net (code "7") (name "Net-(LED1-PadA)") (class "Default")
      (node (ref "LED1") (pin "A") (pinfunction "A_A") (pintype "passive"))
      (node (ref "R9") (pin "2") (pinfunction "2_2") (pintype "passive"))
    )
    (net (code "8") (name "Net-(LED2-PadA)") (class "Default")
      (node (ref "LED2") (pin "A") (pinfunction "A_A") (pintype "passive"))
      (node (ref "R8") (pin "2") (pinfunction "2_2") (pintype "passive"))
    )
    (net (code "9") (name "Net-(LED4-PadA)") (class "Default")
      (node (ref "LED4") (pin "A") (pinfunction "A_A") (pintype "passive"))
      (node (ref "R17") (pin "2") (pinfunction "2_2") (pintype "passive"))
    )
    (net (code "10") (name "Net-(R1-Pad1)") (class "Default")
      (node (ref "R1") (pin "1") (pinfunction "1_1") (pintype "passive"))
      (node (ref "U$6") (pin "RES12K/31") (pinfunction "RES12K/31_RES12K/31") (pintype "bidirectional"))
    )
    (net (code "11") (name "Net-(R5-Pad2)") (class "Default")
      (node (ref "R5") (pin "2") (pinfunction "2_2") (pintype "passive"))
      (node (ref "U$6") (pin "MTCK/12") (pinfunction "MTCK/12_MTCK/12") (pintype "bidirectional"))
    )
    (net (code "12") (name "Net-(R18-Pad2)") (class "Default")
      (node (ref "R18") (pin "2") (pinfunction "2_2") (pintype "passive"))
      (node (ref "U$6") (pin "SD_CLK/21") (pinfunction "SD_CLK/21_SD_CLK/21") (pintype "bidirectional"))
    )
    (net (code "13") (name "Net-(R25-Pad2)") (class "Default")
      (node (ref "R25") (pin "2") (pinfunction "2_2") (pintype "passive"))
      (node (ref "U$8") (pin "G") (pinfunction "G_G") (pintype "bidirectional"))
    )
    (net (code "14") (name "Net-(R26-Pad2)") (class "Default")
      (node (ref "R26") (pin "2") (pinfunction "2_2") (pintype "passive"))
      (node (ref "U$8") (pin "R") (pinfunction "R_R") (pintype "bidirectional"))
    )
    (net (code "15") (name "Net-(R27-Pad2)") (class "Default")
      (node (ref "R27") (pin "2") (pinfunction "2_2") (pintype "passive"))
      (node (ref "U$8") (pin "B") (pinfunction "B_B") (pintype "bidirectional"))
    )
    (net (code "16") (name "Net-(R28-Pad2)") (class "Default")
      (node (ref "R28") (pin "2") (pinfunction "2_2") (pintype "passive"))
      (node (ref "U$11") (pin "B") (pinfunction "B_B") (pintype "bidirectional"))
    )
    (net (code "17") (name "Net-(R29-Pad2)") (class "Default")
      (node (ref "R29") (pin "2") (pinfunction "2_2") (pintype "passive"))
      (node (ref "U$11") (pin "R") (pinfunction "R_R") (pintype "bidirectional"))
    )
    (net (code "18") (name "Net-(R30-Pad2)") (class "Default")
      (node (ref "R30") (pin "2") (pinfunction "2_2") (pintype "passive"))
      (node (ref "U$11") (pin "G") (pinfunction "G_G") (pintype "bidirectional"))
    )
    (net (code "19") (name "Net-(R31-Pad2)") (class "Default")
      (node (ref "R31") (pin "2") (pinfunction "2_2") (pintype "passive"))
      (node (ref "U$13") (pin "B") (pinfunction "B_B") (pintype "bidirectional"))
    )
    (net (code "20") (name "Net-(R32-Pad2)") (class "Default")
      (node (ref "R32") (pin "2") (pinfunction "2_2") (pintype "passive"))
      (node (ref "U$13") (pin "R") (pinfunction "R_R") (pintype "bidirectional"))
    )
    (net (code "21") (name "Net-(R33-Pad2)") (class "Default")
      (node (ref "R33") (pin "2") (pinfunction "2_2") (pintype "passive"))
      (node (ref "U$13") (pin "G") (pinfunction "G_G") (pintype "bidirectional"))
    )
    (net (code "22") (name "Net-(R34-Pad2)") (class "Default")
      (node (ref "R34") (pin "2") (pinfunction "2_2") (pintype "passive"))
      (node (ref "U$14") (pin "B") (pinfunction "B_B") (pintype "bidirectional"))
    )
    (net (code "23") (name "Net-(R35-Pad2)") (class "Default")
      (node (ref "R35") (pin "2") (pinfunction "2_2") (pintype "passive"))
      (node (ref "U$14") (pin "R") (pinfunction "R_R") (pintype "bidirectional"))
    )
    (net (code "24") (name "Net-(R36-Pad2)") (class "Default")
      (node (ref "R36") (pin "2") (pinfunction "2_2") (pintype "passive"))
      (node (ref "U$14") (pin "G") (pinfunction "G_G") (pintype "bidirectional"))
    )
    (net (code "25") (name "Net-(R37-Pad2)") (class "Default")
      (node (ref "R37") (pin "2") (pinfunction "2_2") (pintype "passive"))
      (node (ref "U$15") (pin "B") (pinfunction "B_B") (pintype "bidirectional"))
    )
    (net (code "26") (name "Net-(R38-Pad2)") (class "Default")
      (node (ref "R38") (pin "2") (pinfunction "2_2") (pintype "passive"))
      (node (ref "U$15") (pin "R") (pinfunction "R_R") (pintype "bidirectional"))
    )
    (net (code "27") (name "Net-(R39-Pad2)") (class "Default")
      (node (ref "R39") (pin "2") (pinfunction "2_2") (pintype "passive"))
      (node (ref "U$15") (pin "G") (pinfunction "G_G") (pintype "bidirectional"))
    )
    (net (code "28") (name "Net-(R40-Pad2)") (class "Default")
      (node (ref "R40") (pin "2") (pinfunction "2_2") (pintype "passive"))
      (node (ref "U$16") (pin "B") (pinfunction "B_B") (pintype "bidirectional"))
    )
    (net (code "29") (name "Net-(R41-Pad2)") (class "Default")
      (node (ref "R41") (pin "2") (pinfunction "2_2") (pintype "passive"))
      (node (ref "U$16") (pin "R") (pinfunction "R_R") (pintype "bidirectional"))
    )
    (net (code "30") (name "Net-(R42-Pad2)") (class "Default")
      (node (ref "R42") (pin "2") (pinfunction "2_2") (pintype "passive"))
      (node (ref "U$16") (pin "G") (pinfunction "G_G") (pintype "bidirectional"))
    )
    (net (code "31") (name "Net-(R43-Pad2)") (class "Default")
      (node (ref "R43") (pin "2") (pinfunction "2_2") (pintype "passive"))
      (node (ref "U$17") (pin "B") (pinfunction "B_B") (pintype "bidirectional"))
    )
    (net (code "32") (name "Net-(R44-Pad2)") (class "Default")
      (node (ref "R44") (pin "2") (pinfunction "2_2") (pintype "passive"))
      (node (ref "U$17") (pin "R") (pinfunction "R_R") (pintype "bidirectional"))
    )
    (net (code "33") (name "Net-(R45-Pad2)") (class "Default")
      (node (ref "R45") (pin "2") (pinfunction "2_2") (pintype "passive"))
      (node (ref "U$17") (pin "G") (pinfunction "G_G") (pintype "bidirectional"))
    )
    (net (code "34") (name "Net-(R46-Pad2)") (class "Default")
      (node (ref "R46") (pin "2") (pinfunction "2_2") (pintype "passive"))
      (node (ref "U$18") (pin "B") (pinfunction "B_B") (pintype "bidirectional"))
    )
    (net (code "35") (name "Net-(R47-Pad2)") (class "Default")
      (node (ref "R47") (pin "2") (pinfunction "2_2") (pintype "passive"))
      (node (ref "U$18") (pin "R") (pinfunction "R_R") (pintype "bidirectional"))
    )
    (net (code "36") (name "Net-(R48-Pad2)") (class "Default")
      (node (ref "R48") (pin "2") (pinfunction "2_2") (pintype "passive"))
      (node (ref "U$18") (pin "G") (pinfunction "G_G") (pintype "bidirectional"))
    )
    (net (code "37") (name "Net-(R51-Pad2)") (class "Default")
      (node (ref "R51") (pin "2") (pinfunction "2_2") (pintype "passive"))
      (node (ref "U$6") (pin "MTDO/13") (pinfunction "MTDO/13_MTDO/13") (pintype "bidirectional"))
    )
    (net (code "38") (name "Net-(S1-O)") (class "Default")
      (node (ref "JP5") (pin "2") (pinfunction "2_2") (pintype "passive"))
      (node (ref "S1") (pin "1") (pinfunction "O_1") (pintype "passive"))
    )
    (net (code "39") (name "Net-(U$1-SIGNAL)") (class "Default")
      (node (ref "C6") (pin "1") (pinfunction "1_1") (pintype "passive"))
      (node (ref "L7") (pin "1") (pinfunction "1_1") (pintype "passive"))
      (node (ref "U$1") (pin "FEED") (pinfunction "SIGNAL_FEED") (pintype "bidirectional"))
    )
    (net (code "40") (name "Net-(U$2-SIGNAL)") (class "Default")
      (node (ref "C12") (pin "1") (pinfunction "1_1") (pintype "passive"))
      (node (ref "C13") (pin "2") (pinfunction "2_2") (pintype "passive"))
      (node (ref "U$2") (pin "FEED") (pinfunction "SIGNAL_FEED") (pintype "bidirectional"))
    )
    (net (code "41") (name "Net-(U$3-CLK)") (class "Default")
      (node (ref "R18") (pin "1") (pinfunction "1_1") (pintype "passive"))
      (node (ref "U$3") (pin "6") (pinfunction "CLK_6") (pintype "bidirectional"))
    )
    (net (code "42") (name "Net-(U$3-CS#)") (class "Default")
      (node (ref "U$3") (pin "1") (pinfunction "CS#_1") (pintype "bidirectional"))
      (node (ref "U$6") (pin "SD_CMD/20") (pinfunction "SD_CMD/20_SD_CMD/20") (pintype "bidirectional"))
    )
    (net (code "43") (name "Net-(U$3-DIO)") (class "Default")
      (node (ref "U$3") (pin "5") (pinfunction "DIO_5") (pintype "bidirectional"))
      (node (ref "U$6") (pin "SD_DATA_1/23") (pinfunction "SD_DATA_1/23_SD_DATA_1/23") (pintype "bidirectional"))
    )
    (net (code "44") (name "Net-(U$3-DO)") (class "Default")
      (node (ref "U$3") (pin "2") (pinfunction "DO_2") (pintype "bidirectional"))
      (node (ref "U$6") (pin "SD_DATA_0/22") (pinfunction "SD_DATA_0/22_SD_DATA_0/22") (pintype "bidirectional"))
    )
    (net (code "45") (name "Net-(U$3-HOLD#)") (class "Default")
      (node (ref "U$3") (pin "7") (pinfunction "HOLD#_7") (pintype "bidirectional"))
      (node (ref "U$6") (pin "SD_DATA_2/18") (pinfunction "SD_DATA_2/18_SD_DATA_2/18") (pintype "bidirectional"))
    )
    (net (code "46") (name "Net-(U$3-WP#)") (class "Default")
      (node (ref "U$3") (pin "3") (pinfunction "WP#_3") (pintype "bidirectional"))
      (node (ref "U$6") (pin "SD_DATA_3/19") (pinfunction "SD_DATA_3/19_SD_DATA_3/19") (pintype "bidirectional"))
    )
    (net (code "47") (name "Net-(U$4-ANT1{slash}12)") (class "Default")
      (node (ref "L2") (pin "1") (pinfunction "1_1") (pintype "passive"))
      (node (ref "L5") (pin "2") (pinfunction "2_2") (pintype "passive"))
      (node (ref "U$4") (pin "12") (pinfunction "ANT1/12_12") (pintype "bidirectional"))
    )
    (net (code "48") (name "Net-(U$4-ANT2{slash}13)") (class "Default")
      (node (ref "L5") (pin "1") (pinfunction "1_1") (pintype "passive"))
      (node (ref "L6") (pin "1") (pinfunction "1_1") (pintype "passive"))
      (node (ref "U$4") (pin "13") (pinfunction "ANT2/13_13") (pintype "bidirectional"))
    )
    (net (code "49") (name "Net-(U$4-DVDD{slash}19)") (class "Default")
      (node (ref "C8") (pin "2") (pinfunction "2_2") (pintype "passive"))
      (node (ref "U$4") (pin "19") (pinfunction "DVDD/19_19") (pintype "bidirectional"))
    )
    (net (code "50") (name "Net-(U$4-IREF{slash}16)") (class "Default")
      (node (ref "R12") (pin "1") (pinfunction "1_1") (pintype "passive"))
      (node (ref "U$4") (pin "16") (pinfunction "IREF/16_16") (pintype "bidirectional"))
    )
    (net (code "51") (name "Net-(U$4-VDD_PA{slash}11)") (class "Default")
      (node (ref "C10") (pin "1") (pinfunction "1_1") (pintype "passive"))
      (node (ref "C9") (pin "1") (pinfunction "1_1") (pintype "passive"))
      (node (ref "L2") (pin "2") (pinfunction "2_2") (pintype "passive"))
      (node (ref "U$4") (pin "11") (pinfunction "VDD_PA/11_11") (pintype "bidirectional"))
    )
    (net (code "52") (name "Net-(U$4-XC1{slash}10)") (class "Default")
      (node (ref "C15") (pin "1") (pinfunction "1_1") (pintype "passive"))
      (node (ref "R11") (pin "2") (pinfunction "2_2") (pintype "passive"))
      (node (ref "U$4") (pin "10") (pinfunction "XC1/10_10") (pintype "bidirectional"))
      (node (ref "Y4") (pin "3") (pinfunction "2_3") (pintype "passive"))
    )
    (net (code "53") (name "Net-(U$4-XC2{slash}9)") (class "Default")
      (node (ref "C14") (pin "1") (pinfunction "1_1") (pintype "passive"))
      (node (ref "R11") (pin "1") (pinfunction "1_1") (pintype "passive"))
      (node (ref "U$4") (pin "9") (pinfunction "XC2/9_9") (pintype "bidirectional"))
      (node (ref "Y4") (pin "1") (pinfunction "1_1") (pintype "passive"))
    )
    (net (code "54") (name "Net-(U$7-NC{slash}TDI)") (class "Default")
      (node (ref "R52") (pin "2") (pinfunction "2_2") (pintype "passive"))
      (node (ref "U$7") (pin "8") (pinfunction "NC/TDI_8") (pintype "bidirectional"))
      (node (ref "U1") (pin "23") (pinfunction "PTA1_23") (pintype "bidirectional"))
    )
    (net (code "55") (name "Net-(U$7-SWO{slash}TDO)") (class "Default")
      (node (ref "U$7") (pin "6") (pinfunction "SWO/TDO_6") (pintype "bidirectional"))
      (node (ref "U1") (pin "24") (pinfunction "PTA2_24") (pintype "bidirectional"))
    )
    (net (code "56") (name "Net-(U$7-~{RESET})") (class "Default")
      (node (ref "R53") (pin "2") (pinfunction "2_2") (pintype "passive"))
      (node (ref "U$7") (pin "10") (pinfunction "~{RESET}_10") (pintype "bidirectional"))
      (node (ref "U1") (pin "34") (pinfunction "RESET_B_34") (pintype "bidirectional"))
    )
    (net (code "57") (name "Net-(U$20-A0)") (class "Default")
      (node (ref "R21") (pin "1") (pinfunction "1_1") (pintype "passive"))
      (node (ref "U$20") (pin "22") (pinfunction "A0_22") (pintype "bidirectional"))
    )
    (net (code "58") (name "Net-(U$20-A1)") (class "Default")
      (node (ref "R20") (pin "1") (pinfunction "1_1") (pintype "passive"))
      (node (ref "U$20") (pin "23") (pinfunction "A1_23") (pintype "bidirectional"))
    )
    (net (code "59") (name "Net-(U$20-A2)") (class "Default")
      (node (ref "R19") (pin "1") (pinfunction "1_1") (pintype "passive"))
      (node (ref "U$20") (pin "24") (pinfunction "A2_24") (pintype "bidirectional"))
    )
    (net (code "60") (name "Net-(U$20-LED0)") (class "Default")
      (node (ref "R26") (pin "1") (pinfunction "1_1") (pintype "passive"))
      (node (ref "U$20") (pin "1") (pinfunction "LED0_1") (pintype "bidirectional"))
    )
    (net (code "61") (name "Net-(U$20-LED1)") (class "Default")
      (node (ref "R25") (pin "1") (pinfunction "1_1") (pintype "passive"))
      (node (ref "U$20") (pin "2") (pinfunction "LED1_2") (pintype "bidirectional"))
    )
    (net (code "62") (name "Net-(U$20-LED2)") (class "Default")
      (node (ref "R27") (pin "1") (pinfunction "1_1") (pintype "passive"))
      (node (ref "U$20") (pin "3") (pinfunction "LED2_3") (pintype "bidirectional"))
    )
    (net (code "63") (name "Net-(U$20-LED3)") (class "Default")
      (node (ref "R29") (pin "1") (pinfunction "1_1") (pintype "passive"))
      (node (ref "U$20") (pin "4") (pinfunction "LED3_4") (pintype "bidirectional"))
    )
    (net (code "64") (name "Net-(U$20-LED4)") (class "Default")
      (node (ref "R30") (pin "1") (pinfunction "1_1") (pintype "passive"))
      (node (ref "U$20") (pin "5") (pinfunction "LED4_5") (pintype "bidirectional"))
    )
    (net (code "65") (name "Net-(U$20-LED5)") (class "Default")
      (node (ref "R28") (pin "1") (pinfunction "1_1") (pintype "passive"))
      (node (ref "U$20") (pin "6") (pinfunction "LED5_6") (pintype "bidirectional"))
    )
    (net (code "66") (name "Net-(U$20-LED6)") (class "Default")
      (node (ref "R32") (pin "1") (pinfunction "1_1") (pintype "passive"))
      (node (ref "U$20") (pin "7") (pinfunction "LED6_7") (pintype "bidirectional"))
    )
    (net (code "67") (name "Net-(U$20-LED7)") (class "Default")
      (node (ref "R33") (pin "1") (pinfunction "1_1") (pintype "passive"))
      (node (ref "U$20") (pin "8") (pinfunction "LED7_8") (pintype "bidirectional"))
    )
    (net (code "68") (name "Net-(U$20-LED8)") (class "Default")
      (node (ref "R31") (pin "1") (pinfunction "1_1") (pintype "passive"))
      (node (ref "U$20") (pin "10") (pinfunction "LED8_10") (pintype "bidirectional"))
    )
    (net (code "69") (name "Net-(U$20-LED9)") (class "Default")
      (node (ref "R35") (pin "1") (pinfunction "1_1") (pintype "passive"))
      (node (ref "U$20") (pin "11") (pinfunction "LED9_11") (pintype "bidirectional"))
    )
    (net (code "70") (name "Net-(U$20-LED10)") (class "Default")
      (node (ref "R36") (pin "1") (pinfunction "1_1") (pintype "passive"))
      (node (ref "U$20") (pin "12") (pinfunction "LED10_12") (pintype "bidirectional"))
    )
    (net (code "71") (name "Net-(U$20-LED11)") (class "Default")
      (node (ref "R34") (pin "1") (pinfunction "1_1") (pintype "passive"))
      (node (ref "U$20") (pin "13") (pinfunction "LED11_13") (pintype "bidirectional"))
    )
    (net (code "72") (name "Net-(U$20-LED12)") (class "Default")
      (node (ref "JP3") (pin "4") (pinfunction "4_4") (pintype "passive"))
      (node (ref "U$20") (pin "14") (pinfunction "LED12_14") (pintype "bidirectional"))
    )
    (net (code "73") (name "Net-(U$20-LED13)") (class "Default")
      (node (ref "JP3") (pin "3") (pinfunction "3_3") (pintype "passive"))
      (node (ref "U$20") (pin "15") (pinfunction "LED13_15") (pintype "bidirectional"))
    )
    (net (code "74") (name "Net-(U$20-LED14)") (class "Default")
      (node (ref "JP3") (pin "2") (pinfunction "2_2") (pintype "passive"))
      (node (ref "U$20") (pin "16") (pinfunction "LED14_16") (pintype "bidirectional"))
    )
    (net (code "75") (name "Net-(U$20-LED15)") (class "Default")
      (node (ref "JP3") (pin "1") (pinfunction "1_1") (pintype "passive"))
      (node (ref "U$20") (pin "17") (pinfunction "LED15_17") (pintype "bidirectional"))
    )
    (net (code "76") (name "Net-(U$21-A0)") (class "Default")
      (node (ref "R22") (pin "1") (pinfunction "1_1") (pintype "passive"))
      (node (ref "U$21") (pin "22") (pinfunction "A0_22") (pintype "bidirectional"))
    )
    (net (code "77") (name "Net-(U$21-A1)") (class "Default")
      (node (ref "R23") (pin "1") (pinfunction "1_1") (pintype "passive"))
      (node (ref "U$21") (pin "23") (pinfunction "A1_23") (pintype "bidirectional"))
    )
    (net (code "78") (name "Net-(U$21-A2)") (class "Default")
      (node (ref "R24") (pin "1") (pinfunction "1_1") (pintype "passive"))
      (node (ref "U$21") (pin "24") (pinfunction "A2_24") (pintype "bidirectional"))
    )
    (net (code "79") (name "Net-(U$21-LED0)") (class "Default")
      (node (ref "R38") (pin "1") (pinfunction "1_1") (pintype "passive"))
      (node (ref "U$21") (pin "1") (pinfunction "LED0_1") (pintype "bidirectional"))
    )
    (net (code "80") (name "Net-(U$21-LED1)") (class "Default")
      (node (ref "R39") (pin "1") (pinfunction "1_1") (pintype "passive"))
      (node (ref "U$21") (pin "2") (pinfunction "LED1_2") (pintype "bidirectional"))
    )
    (net (code "81") (name "Net-(U$21-LED2)") (class "Default")
      (node (ref "R37") (pin "1") (pinfunction "1_1") (pintype "passive"))
      (node (ref "U$21") (pin "3") (pinfunction "LED2_3") (pintype "bidirectional"))
    )
    (net (code "82") (name "Net-(U$21-LED3)") (class "Default")
      (node (ref "R41") (pin "1") (pinfunction "1_1") (pintype "passive"))
      (node (ref "U$21") (pin "4") (pinfunction "LED3_4") (pintype "bidirectional"))
    )
    (net (code "83") (name "Net-(U$21-LED4)") (class "Default")
      (node (ref "R42") (pin "1") (pinfunction "1_1") (pintype "passive"))
      (node (ref "U$21") (pin "5") (pinfunction "LED4_5") (pintype "bidirectional"))
    )
    (net (code "84") (name "Net-(U$21-LED5)") (class "Default")
      (node (ref "R40") (pin "1") (pinfunction "1_1") (pintype "passive"))
      (node (ref "U$21") (pin "6") (pinfunction "LED5_6") (pintype "bidirectional"))
    )
    (net (code "85") (name "Net-(U$21-LED6)") (class "Default")
      (node (ref "R44") (pin "1") (pinfunction "1_1") (pintype "passive"))
      (node (ref "U$21") (pin "7") (pinfunction "LED6_7") (pintype "bidirectional"))
    )
    (net (code "86") (name "Net-(U$21-LED7)") (class "Default")
      (node (ref "R45") (pin "1") (pinfunction "1_1") (pintype "passive"))
      (node (ref "U$21") (pin "8") (pinfunction "LED7_8") (pintype "bidirectional"))
    )
    (net (code "87") (name "Net-(U$21-LED8)") (class "Default")
      (node (ref "R43") (pin "1") (pinfunction "1_1") (pintype "passive"))
      (node (ref "U$21") (pin "10") (pinfunction "LED8_10") (pintype "bidirectional"))
    )
    (net (code "88") (name "Net-(U$21-LED9)") (class "Default")
      (node (ref "R47") (pin "1") (pinfunction "1_1") (pintype "passive"))
      (node (ref "U$21") (pin "11") (pinfunction "LED9_11") (pintype "bidirectional"))
    )
    (net (code "89") (name "Net-(U$21-LED10)") (class "Default")
      (node (ref "R48") (pin "1") (pinfunction "1_1") (pintype "passive"))
      (node (ref "U$21") (pin "12") (pinfunction "LED10_12") (pintype "bidirectional"))
    )
    (net (code "90") (name "Net-(U$21-LED11)") (class "Default")
      (node (ref "R46") (pin "1") (pinfunction "1_1") (pintype "passive"))
      (node (ref "U$21") (pin "13") (pinfunction "LED11_13") (pintype "bidirectional"))
    )
    (net (code "91") (name "Net-(U1-EXTAL32)") (class "Default")
      (node (ref "C32") (pin "2") (pinfunction "2_2") (pintype "passive"))
      (node (ref "U1") (pin "20") (pinfunction "EXTAL32_20") (pintype "bidirectional"))
      (node (ref "Y1") (pin "P$1") (pinfunction "1_P$1") (pintype "passive"))
    )
    (net (code "92") (name "Net-(U1-PTA18)") (class "Default")
      (node (ref "C29") (pin "2") (pinfunction "2_2") (pintype "passive"))
      (node (ref "U1") (pin "32") (pinfunction "PTA18_32") (pintype "bidirectional"))
      (node (ref "Y2") (pin "3") (pinfunction "2_3") (pintype "passive"))
    )
    (net (code "93") (name "Net-(U1-PTA19)") (class "Default")
      (node (ref "C30") (pin "2") (pinfunction "2_2") (pintype "passive"))
      (node (ref "U1") (pin "33") (pinfunction "PTA19_33") (pintype "bidirectional"))
      (node (ref "Y2") (pin "1") (pinfunction "1_1") (pintype "passive"))
    )
    (net (code "94") (name "Net-(U1-PTD6)") (class "Default")
      (node (ref "R8") (pin "1") (pinfunction "1_1") (pintype "passive"))
      (node (ref "U1") (pin "63") (pinfunction "PTD6_63") (pintype "bidirectional"))
    )
    (net (code "95") (name "Net-(U1-PTD7)") (class "Default")
      (node (ref "R17") (pin "1") (pinfunction "1_1") (pintype "passive"))
      (node (ref "U1") (pin "64") (pinfunction "PTD7_64") (pintype "bidirectional"))
    )
    (net (code "96") (name "Net-(U1-VDDA)") (class "Default")
      (node (ref "C17") (pin "1") (pinfunction "1_1") (pintype "passive"))
      (node (ref "L3") (pin "1") (pinfunction "1_1") (pintype "passive"))
      (node (ref "R16") (pin "1") (pinfunction "1_1") (pintype "passive"))
      (node (ref "U1") (pin "13") (pinfunction "VDDA_13") (pintype "bidirectional"))
    )
    (net (code "97") (name "Net-(U1-VREFH)") (class "Default")
      (node (ref "C11") (pin "1") (pinfunction "1_1") (pintype "passive"))
      (node (ref "R16") (pin "2") (pinfunction "2_2") (pintype "passive"))
      (node (ref "U1") (pin "14") (pinfunction "VREFH_14") (pintype "bidirectional"))
    )
    (net (code "98") (name "Net-(U1-VREFL)") (class "Default")
      (node (ref "C11") (pin "2") (pinfunction "2_2") (pintype "passive"))
      (node (ref "C16") (pin "2") (pinfunction "2_2") (pintype "passive"))
      (node (ref "C17") (pin "2") (pinfunction "2_2") (pintype "passive"))
      (node (ref "L4") (pin "2") (pinfunction "2_2") (pintype "passive"))
      (node (ref "U1") (pin "15") (pinfunction "VREFL_15") (pintype "bidirectional"))
      (node (ref "U1") (pin "16") (pinfunction "VSSA_16") (pintype "bidirectional"))
    )
    (net (code "99") (name "Net-(U1-VREF_OUT)") (class "Default")
      (node (ref "C16") (pin "1") (pinfunction "1_1") (pintype "passive"))
      (node (ref "U1") (pin "17") (pinfunction "VREF_OUT_17") (pintype "bidirectional"))
    )
    (net (code "100") (name "Net-(U1-XTAL32)") (class "Default")
      (node (ref "C31") (pin "2") (pinfunction "2_2") (pintype "passive"))
      (node (ref "U1") (pin "19") (pinfunction "XTAL32_19") (pintype "bidirectional"))
      (node (ref "Y1") (pin "P$2") (pinfunction "2_P$2") (pintype "passive"))
    )
    (net (code "101") (name "Net-(U2-FB)") (class "Default")
      (node (ref "R6") (pin "2") (pinfunction "2_2") (pintype "passive"))
      (node (ref "R7") (pin "1") (pinfunction "1_1") (pintype "passive"))
      (node (ref "U2") (pin "10") (pinfunction "FB_10") (pintype "passive"))
    )
    (net (code "102") (name "Net-(U2-L)") (class "Default")
      (node (ref "L1") (pin "1") (pinfunction "1_1") (pintype "passive"))
      (node (ref "U2") (pin "3") (pinfunction "L_3") (pintype "passive"))
    )
    (net (code "103") (name "Net-(U2-UVLO)") (class "Default")
      (node (ref "C2") (pin "2") (pinfunction "2_2") (pintype "passive"))
      (node (ref "R3") (pin "1") (pinfunction "1_1") (pintype "passive"))
      (node (ref "R4") (pin "2") (pinfunction "2_2") (pintype "passive"))
      (node (ref "U2") (pin "7") (pinfunction "UVLO_7") (pintype "passive"))
    )
    (net (code "104") (name "Net-(U2-VAUX)") (class "Default")
      (node (ref "C4") (pin "1") (pinfunction "1_1") (pintype "passive"))
      (node (ref "U2") (pin "1") (pinfunction "VAUX_1") (pintype "passive"))
    )
    (net (code "105") (name "Net-(U3-REGOUT)") (class "Default")
      (node (ref "C27") (pin "2") (pinfunction "2_2") (pintype "passive"))
      (node (ref "U3") (pin "10") (pinfunction "REGOUT_10") (pintype "bidirectional"))
    )
    (net (code "106") (name "Net-(Y3-2)") (class "Default")
      (node (ref "C23") (pin "1") (pinfunction "1_1") (pintype "passive"))
      (node (ref "U$6") (pin "XTAL_IN/28") (pinfunction "XTAL_IN/28_XTAL_IN/28") (pintype "bidirectional"))
      (node (ref "Y3") (pin "3") (pinfunction "2_3") (pintype "passive"))
    )
    (net (code "107") (name "PS") (class "Default")
      (node (ref "R2") (pin "2") (pinfunction "2_2") (pintype "passive"))
      (node (ref "U2") (pin "8") (pinfunction "PS_8") (pintype "input"))
    )
    (net (code "108") (name "PTA0") (class "Default")
      (node (ref "R50") (pin "2") (pinfunction "2_2") (pintype "passive"))
      (node (ref "U$7") (pin "4") (pinfunction "SWDCLK/TCK_4") (pintype "bidirectional"))
      (node (ref "U1") (pin "22") (pinfunction "PTA0_22") (pintype "bidirectional"))
    )
    (net (code "109") (name "PTA3") (class "Default")
      (node (ref "R49") (pin "2") (pinfunction "2_2") (pintype "passive"))
      (node (ref "U$7") (pin "2") (pinfunction "SWDIO/TMS_2") (pintype "bidirectional"))
      (node (ref "U1") (pin "25") (pinfunction "PTA3_25") (pintype "bidirectional"))
    )
    (net (code "110") (name "PTB0") (class "Default")
      (node (ref "U1") (pin "35") (pinfunction "PTB0_35") (pintype "bidirectional"))
      (node (ref "U3") (pin "12") (pinfunction "INT_12") (pintype "bidirectional"))
    )
    (net (code "111") (name "PTB1") (class "Default")
      (node (ref "U1") (pin "36") (pinfunction "PTB1_36") (pintype "bidirectional"))
      (node (ref "U3") (pin "11") (pinfunction "FSYNC_11") (pintype "bidirectional"))
    )
    (net (code "112") (name "PTB16") (class "Default")
      (node (ref "U$6") (pin "U0TXD/26") (pinfunction "U0TXD/26_U0TXD/26") (pintype "bidirectional"))
      (node (ref "U1") (pin "39") (pinfunction "PTB16_39") (pintype "bidirectional"))
    )
    (net (code "113") (name "PTB17") (class "Default")
      (node (ref "U$6") (pin "U0RXD/25") (pinfunction "U0RXD/25_U0RXD/25") (pintype "bidirectional"))
      (node (ref "U1") (pin "40") (pinfunction "PTB17_40") (pintype "bidirectional"))
    )
    (net (code "114") (name "PTB18") (class "Default")
      (node (ref "U$6") (pin "GPIO0/15") (pinfunction "GPIO0/15_GPIO0/15") (pintype "bidirectional"))
      (node (ref "U1") (pin "41") (pinfunction "PTB18_41") (pintype "bidirectional"))
    )
    (net (code "115") (name "PTB19") (class "Default")
      (node (ref "U$6") (pin "GPIO2/14") (pinfunction "GPIO2/14_GPIO2/14") (pintype "bidirectional"))
      (node (ref "U1") (pin "42") (pinfunction "PTB19_42") (pintype "bidirectional"))
    )
    (net (code "116") (name "PTC0") (class "Default")
      (node (ref "R15") (pin "1") (pinfunction "1_1") (pintype "passive"))
      (node (ref "U$6") (pin "EXT_RSTB/32") (pinfunction "EXT_RSTB/32_EXT_RSTB/32") (pintype "bidirectional"))
      (node (ref "U1") (pin "43") (pinfunction "PTC0_43") (pintype "bidirectional"))
    )
    (net (code "117") (name "PTC1") (class "Default")
      (node (ref "U$6") (pin "CHIP_EN/7") (pinfunction "CHIP_EN/7_CHIP_EN/7") (pintype "bidirectional"))
      (node (ref "U1") (pin "44") (pinfunction "PTC1_44") (pintype "bidirectional"))
    )
    (net (code "118") (name "PTC3") (class "Default")
      (node (ref "U$6") (pin "XPD_DCDC/8") (pinfunction "XPD_DCDC/8_XPD_DCDC/8") (pintype "bidirectional"))
      (node (ref "U1") (pin "46") (pinfunction "PTC3_46") (pintype "bidirectional"))
    )
    (net (code "119") (name "PTC4") (class "Default")
      (node (ref "U$4") (pin "2") (pinfunction "CSN/2_2") (pintype "bidirectional"))
      (node (ref "U1") (pin "49") (pinfunction "PTC4_49") (pintype "bidirectional"))
    )
    (net (code "120") (name "PTC5") (class "Default")
      (node (ref "U$4") (pin "3") (pinfunction "SCK/3_3") (pintype "bidirectional"))
      (node (ref "U1") (pin "50") (pinfunction "PTC5_50") (pintype "bidirectional"))
    )
    (net (code "121") (name "PTC6") (class "Default")
      (node (ref "U$4") (pin "4") (pinfunction "MOSI/4_4") (pintype "bidirectional"))
      (node (ref "U1") (pin "51") (pinfunction "PTC6_51") (pintype "bidirectional"))
    )
    (net (code "122") (name "PTC7") (class "Default")
      (node (ref "U$4") (pin "5") (pinfunction "MISO/5_5") (pintype "bidirectional"))
      (node (ref "U1") (pin "52") (pinfunction "PTC7_52") (pintype "bidirectional"))
    )
    (net (code "123") (name "PTC8") (class "Default")
      (node (ref "U$4") (pin "6") (pinfunction "IRQ/6_6") (pintype "bidirectional"))
      (node (ref "U1") (pin "53") (pinfunction "PTC8_53") (pintype "bidirectional"))
    )
    (net (code "124") (name "PTC9") (class "Default")
      (node (ref "U$4") (pin "1") (pinfunction "CE/1_1") (pintype "bidirectional"))
      (node (ref "U1") (pin "54") (pinfunction "PTC9_54") (pintype "bidirectional"))
    )
    (net (code "125") (name "PTC10") (class "Default")
      (node (ref "JP1") (pin "12") (pinfunction "12_12") (pintype "passive"))
      (node (ref "U1") (pin "55") (pinfunction "PTC10_55") (pintype "bidirectional"))
    )
    (net (code "126") (name "PTC11") (class "Default")
      (node (ref "JP1") (pin "11") (pinfunction "11_11") (pintype "passive"))
      (node (ref "U1") (pin "56") (pinfunction "PTC11_56") (pintype "bidirectional"))
    )
    (net (code "127") (name "PTD0") (class "Default")
      (node (ref "JP1") (pin "10") (pinfunction "10_10") (pintype "passive"))
      (node (ref "U1") (pin "57") (pinfunction "PTD0_57") (pintype "bidirectional"))
    )
    (net (code "128") (name "PTD1") (class "Default")
      (node (ref "JP1") (pin "9") (pinfunction "9_9") (pintype "passive"))
      (node (ref "U1") (pin "58") (pinfunction "PTD1_58") (pintype "bidirectional"))
    )
    (net (code "129") (name "PTD2") (class "Default")
      (node (ref "JP1") (pin "8") (pinfunction "8_8") (pintype "passive"))
      (node (ref "U1") (pin "59") (pinfunction "PTD2_59") (pintype "bidirectional"))
    )
    (net (code "130") (name "PTD3") (class "Default")
      (node (ref "JP1") (pin "7") (pinfunction "7_7") (pintype "passive"))
      (node (ref "U1") (pin "60") (pinfunction "PTD3_60") (pintype "bidirectional"))
    )
    (net (code "131") (name "PTD4") (class "Default")
      (node (ref "JP1") (pin "6") (pinfunction "6_6") (pintype "passive"))
      (node (ref "U1") (pin "61") (pinfunction "PTD4_61") (pintype "bidirectional"))
    )
    (net (code "132") (name "PTD5") (class "Default")
      (node (ref "JP1") (pin "5") (pinfunction "5_5") (pintype "passive"))
      (node (ref "U1") (pin "62") (pinfunction "PTD5_62") (pintype "bidirectional"))
    )
    (net (code "133") (name "SCL") (class "Default")
      (node (ref "R14") (pin "2") (pinfunction "2_2") (pintype "passive"))
      (node (ref "U$20") (pin "19") (pinfunction "SCL_19") (pintype "bidirectional"))
      (node (ref "U$21") (pin "19") (pinfunction "SCL_19") (pintype "bidirectional"))
      (node (ref "U1") (pin "37") (pinfunction "PTB2_37") (pintype "bidirectional"))
      (node (ref "U3") (pin "23") (pinfunction "SCLK_23") (pintype "bidirectional"))
    )
    (net (code "134") (name "SDA") (class "Default")
      (node (ref "R13") (pin "2") (pinfunction "2_2") (pintype "passive"))
      (node (ref "U$20") (pin "20") (pinfunction "SDA_20") (pintype "bidirectional"))
      (node (ref "U$21") (pin "20") (pinfunction "SDA_20") (pintype "bidirectional"))
      (node (ref "U1") (pin "38") (pinfunction "PTB3_38") (pintype "bidirectional"))
      (node (ref "U3") (pin "24") (pinfunction "SDA/MOSI_24") (pintype "bidirectional"))
    )
    (net (code "135") (name "SOFTPOWER") (class "Default")
      (node (ref "R10") (pin "1") (pinfunction "1_1") (pintype "passive"))
      (node (ref "U2") (pin "6") (pinfunction "EN_6") (pintype "input"))
    )
    (net (code "136") (name "USB_D_N") (class "Default")
      (node (ref "U1") (pin "6") (pinfunction "USB0_DM_6") (pintype "bidirectional"))
    )
    (net (code "137") (name "USB_D_P") (class "Default")
      (node (ref "U1") (pin "5") (pinfunction "USB0_DP_5") (pintype "bidirectional"))
    )
    (net (code "138") (name "VCC") (class "Default")
      (node (ref "C1") (pin "1") (pinfunction "1_1") (pintype "passive"))
      (node (ref "C2") (pin "1") (pinfunction "1_1") (pintype "passive"))
      (node (ref "L1") (pin "2") (pinfunction "2_2") (pintype "passive"))
      (node (ref "R10") (pin "2") (pinfunction "2_2") (pintype "passive"))
      (node (ref "R2") (pin "1") (pinfunction "1_1") (pintype "passive"))
      (node (ref "R3") (pin "2") (pinfunction "2_2") (pintype "passive"))
      (node (ref "S1") (pin "2") (pinfunction "P_2") (pintype "passive"))
      (node (ref "U2") (pin "5") (pinfunction "VIN_5") (pintype "power_in"))
    )
    (net (code "139") (name "unconnected-(S1-S-Pad3)") (class "Default")
      (node (ref "S1") (pin "3") (pinfunction "S_3") (pintype "passive"))
    )
    (net (code "140") (name "unconnected-(U$6-PadDVDD{slash}24)") (class "Default")
      (node (ref "U$6") (pin "DVDD/24") (pinfunction "DVDD/24_DVDD/24") (pintype "bidirectional"))
    )
    (net (code "141") (name "unconnected-(U$6-PadMTDI{slash}10)") (class "Default")
      (node (ref "U$6") (pin "MTDI/10") (pinfunction "MTDI/10_MTDI/10") (pintype "bidirectional"))
    )
    (net (code "142") (name "unconnected-(U$6-PadMTMS{slash}9)") (class "Default")
      (node (ref "U$6") (pin "MTMS/9") (pinfunction "MTMS/9_MTMS/9") (pintype "bidirectional"))
    )
    (net (code "143") (name "unconnected-(U$6-PadTOUT{slash}6)") (class "Default")
      (node (ref "U$6") (pin "TOUT/6") (pinfunction "TOUT/6_TOUT/6") (pintype "bidirectional"))
    )
    (net (code "144") (name "unconnected-(U$6-PadVDD_RTC{slash}5)") (class "Default")
      (node (ref "U$6") (pin "VDD_RTC/5") (pinfunction "VDD_RTC/5_VDD_RTC/5") (pintype "bidirectional"))
    )
    (net (code "145") (name "unconnected-(U$6-PadVDD{slash}16)") (class "Default")
      (node (ref "U$6") (pin "VDD/16") (pinfunction "VDD/16_VDD/16") (pintype "bidirectional"))
    )
    (net (code "146") (name "unconnected-(U$20-LED16-Pad18)") (class "Default")
      (node (ref "U$20") (pin "18") (pinfunction "LED16_18") (pintype "bidirectional"))
    )
    (net (code "147") (name "unconnected-(U$21-LED12-Pad14)") (class "Default")
      (node (ref "U$21") (pin "14") (pinfunction "LED12_14") (pintype "bidirectional"))
    )
    (net (code "148") (name "unconnected-(U$21-LED13-Pad15)") (class "Default")
      (node (ref "U$21") (pin "15") (pinfunction "LED13_15") (pintype "bidirectional"))
    )
    (net (code "149") (name "unconnected-(U$21-LED14-Pad16)") (class "Default")
      (node (ref "U$21") (pin "16") (pinfunction "LED14_16") (pintype "bidirectional"))
    )
    (net (code "150") (name "unconnected-(U$21-LED15-Pad17)") (class "Default")
      (node (ref "U$21") (pin "17") (pinfunction "LED15_17") (pintype "bidirectional"))
    )
    (net (code "151") (name "unconnected-(U$21-LED16-Pad18)") (class "Default")
      (node (ref "U$21") (pin "18") (pinfunction "LED16_18") (pintype "bidirectional"))
    )
    (net (code "152") (name "unconnected-(U1-ADC0_DM0-Pad10)") (class "Default")
      (node (ref "U1") (pin "10") (pinfunction "ADC0_DM0_10") (pintype "bidirectional"))
    )
    (net (code "153") (name "unconnected-(U1-ADC0_DM3-Pad12)") (class "Default")
      (node (ref "U1") (pin "12") (pinfunction "ADC0_DM3_12") (pintype "bidirectional"))
    )
    (net (code "154") (name "unconnected-(U1-ADC0_DP0-Pad9)") (class "Default")
      (node (ref "U1") (pin "9") (pinfunction "ADC0_DP0_9") (pintype "bidirectional"))
    )
    (net (code "155") (name "unconnected-(U1-ADC0_DP3-Pad11)") (class "Default")
      (node (ref "U1") (pin "11") (pinfunction "ADC0_DP3_11") (pintype "bidirectional"))
    )
    (net (code "156") (name "unconnected-(U1-DAC0-Pad18)") (class "Default")
      (node (ref "U1") (pin "18") (pinfunction "DAC0_18") (pintype "bidirectional"))
    )
    (net (code "157") (name "unconnected-(U1-PTA4-Pad26)") (class "Default")
      (node (ref "U1") (pin "26") (pinfunction "PTA4_26") (pintype "bidirectional"))
    )
    (net (code "158") (name "unconnected-(U1-PTA5-Pad27)") (class "Default")
      (node (ref "U1") (pin "27") (pinfunction "PTA5_27") (pintype "bidirectional"))
    )
    (net (code "159") (name "unconnected-(U1-PTA12-Pad28)") (class "Default")
      (node (ref "U1") (pin "28") (pinfunction "PTA12_28") (pintype "bidirectional"))
    )
    (net (code "160") (name "unconnected-(U1-PTA13-Pad29)") (class "Default")
      (node (ref "U1") (pin "29") (pinfunction "PTA13_29") (pintype "bidirectional"))
    )
    (net (code "161") (name "unconnected-(U1-PTE0-Pad1)") (class "Default")
      (node (ref "U1") (pin "1") (pinfunction "PTE0_1") (pintype "bidirectional"))
    )
    (net (code "162") (name "unconnected-(U1-PTE1-Pad2)") (class "Default")
      (node (ref "U1") (pin "2") (pinfunction "PTE1_2") (pintype "bidirectional"))
    )
    (net (code "163") (name "unconnected-(U3-AUX_CL-Pad7)") (class "Default")
      (node (ref "U3") (pin "7") (pinfunction "AUX_CL_7") (pintype "bidirectional"))
    )
    (net (code "164") (name "unconnected-(U3-AUX_DA-Pad21)") (class "Default")
      (node (ref "U3") (pin "21") (pinfunction "AUX_DA_21") (pintype "bidirectional"))
    )
  )
)
